# dda.net
KiCad netlist of a schematic drawn in EAGLE
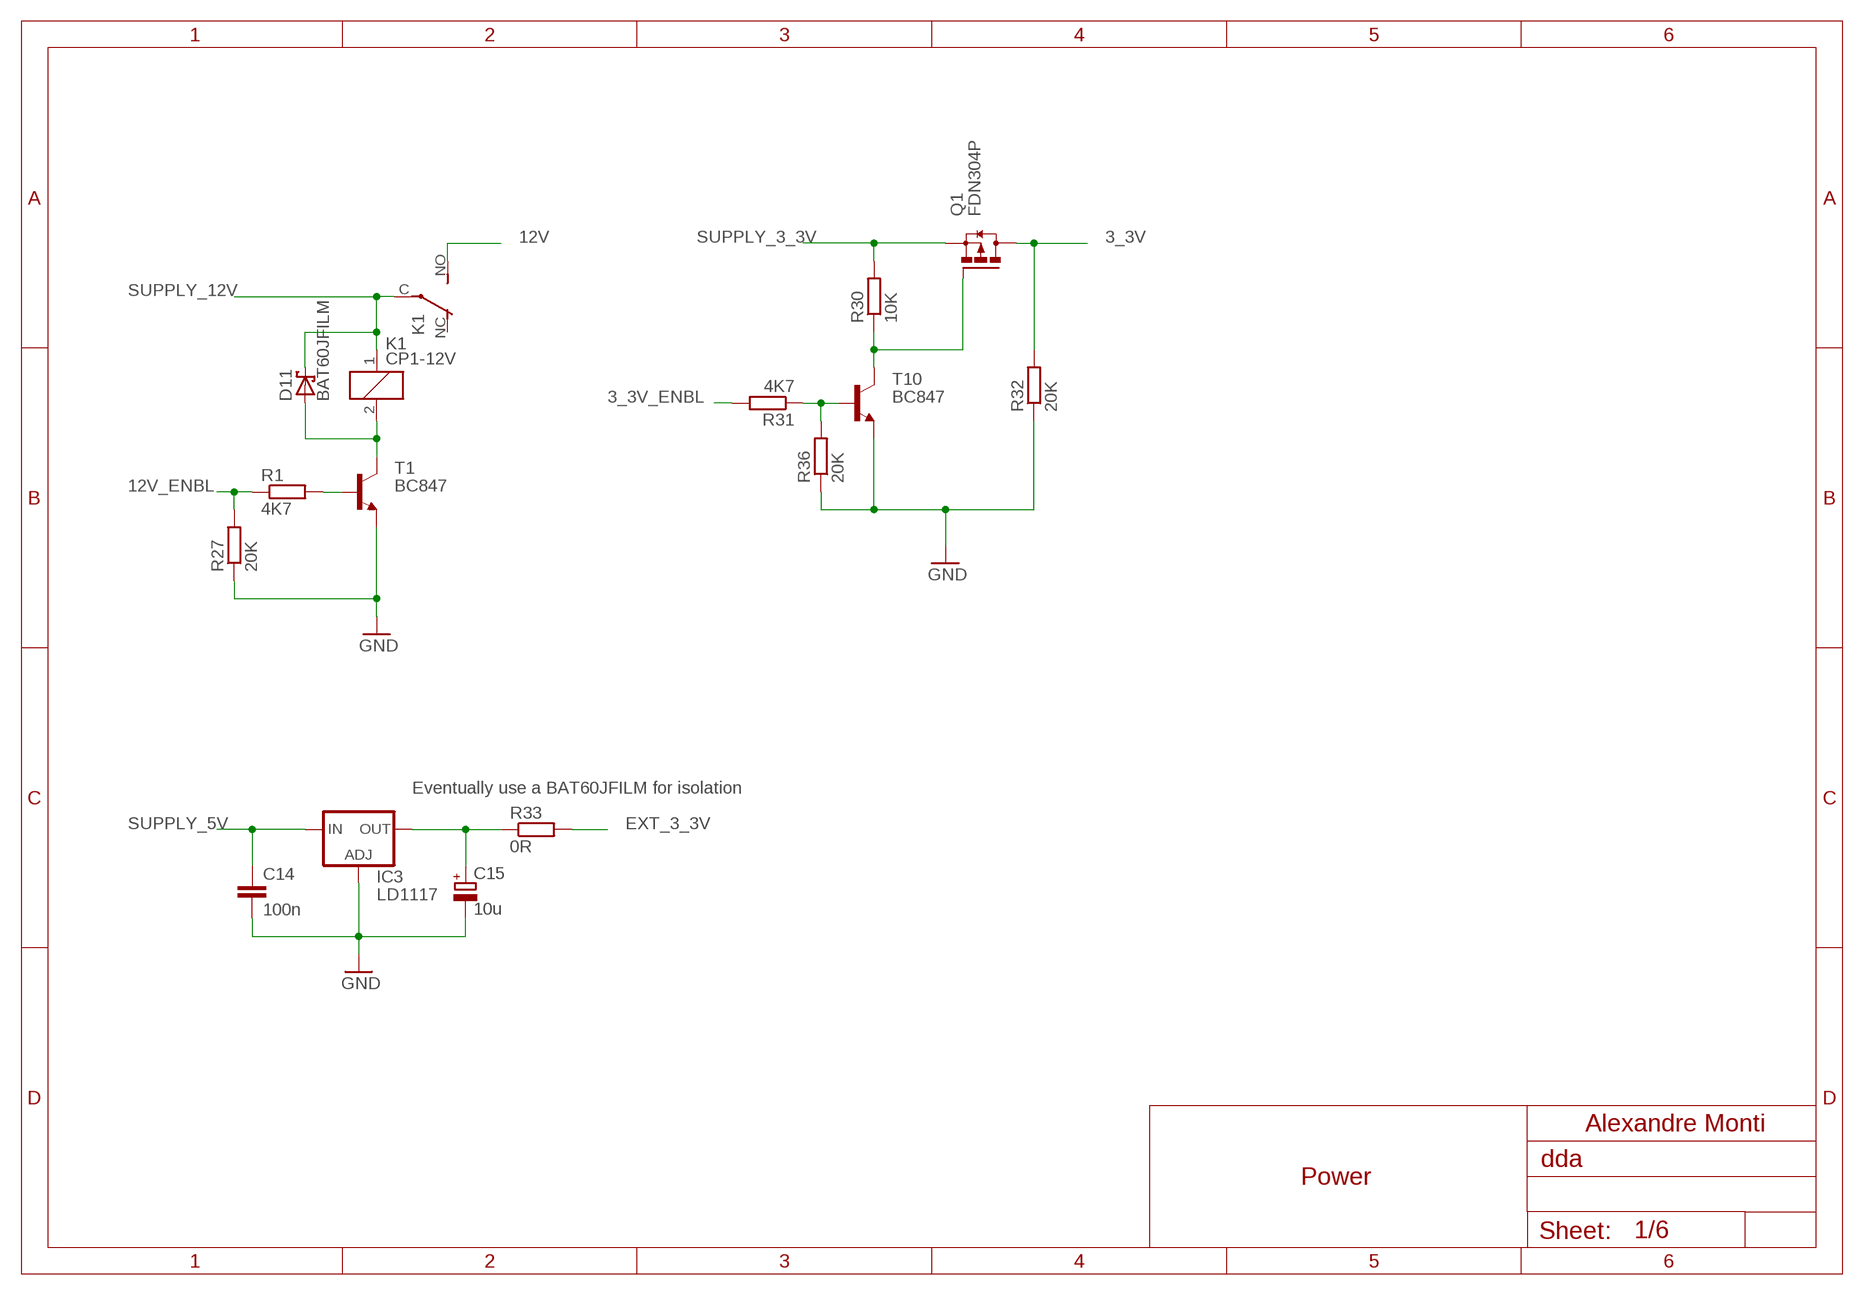
[diagram p0: schematic, sheet 1]
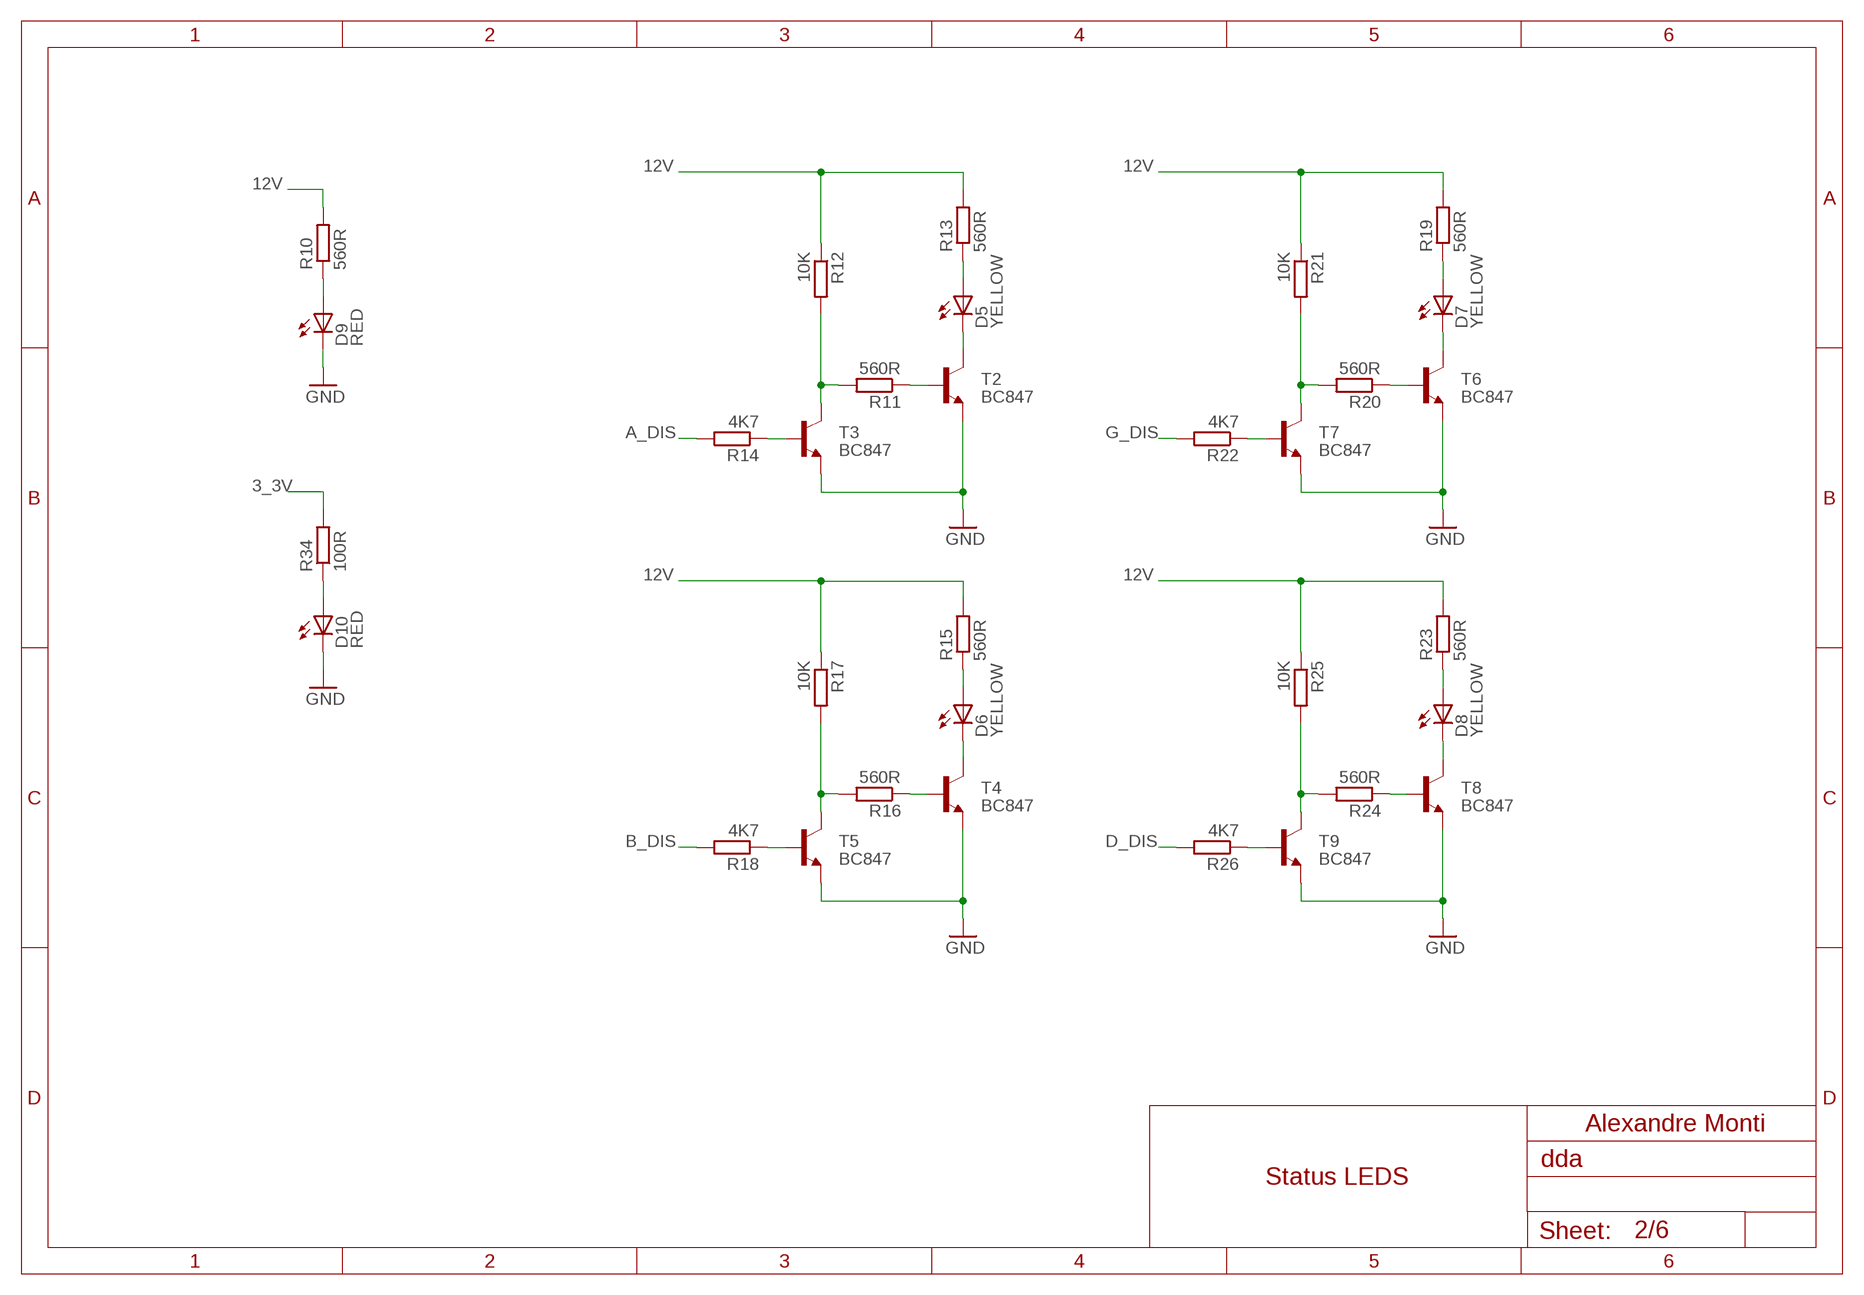
[diagram p1: schematic, sheet 2]
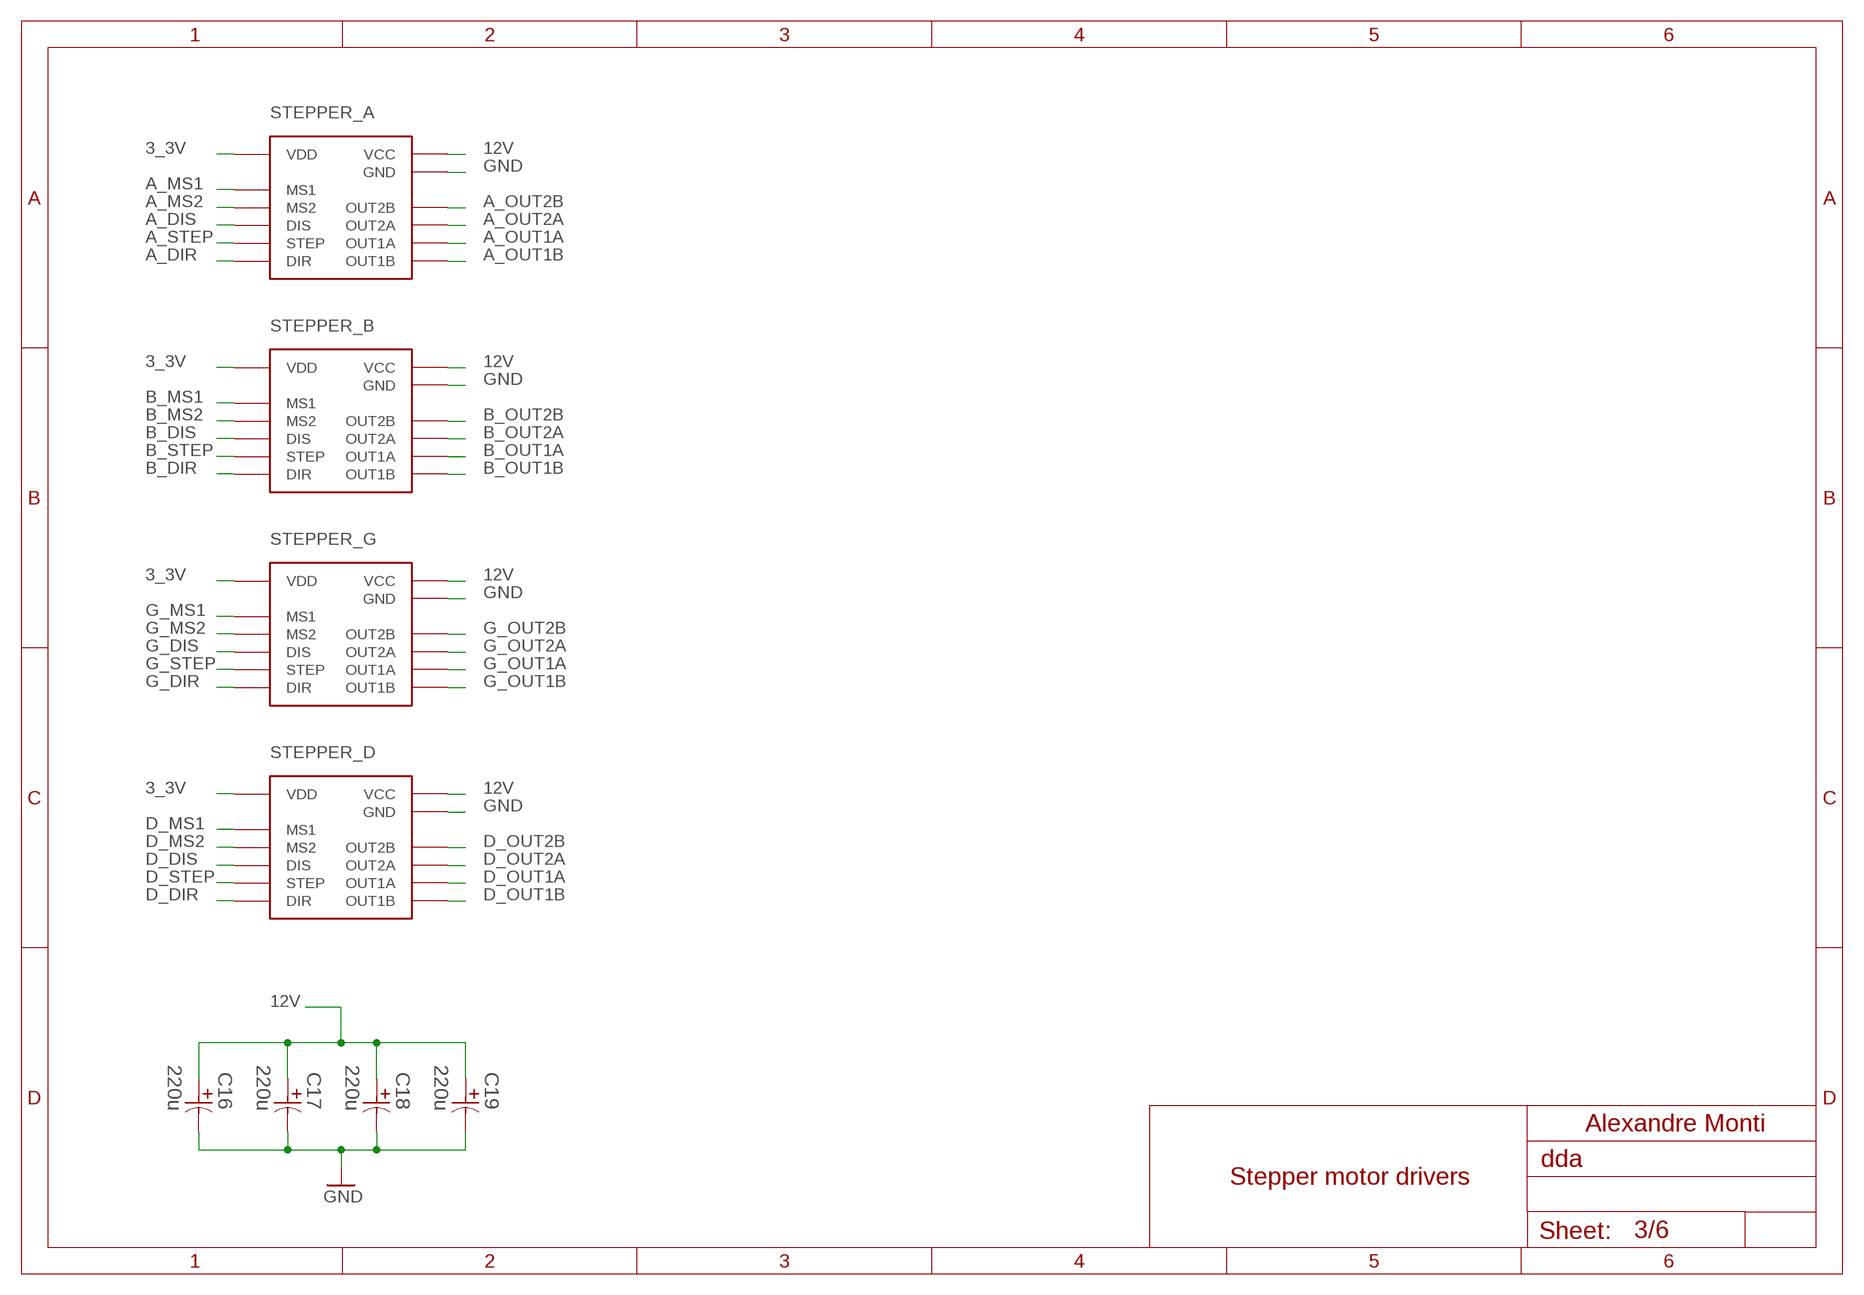
[diagram p2: schematic, sheet 3]
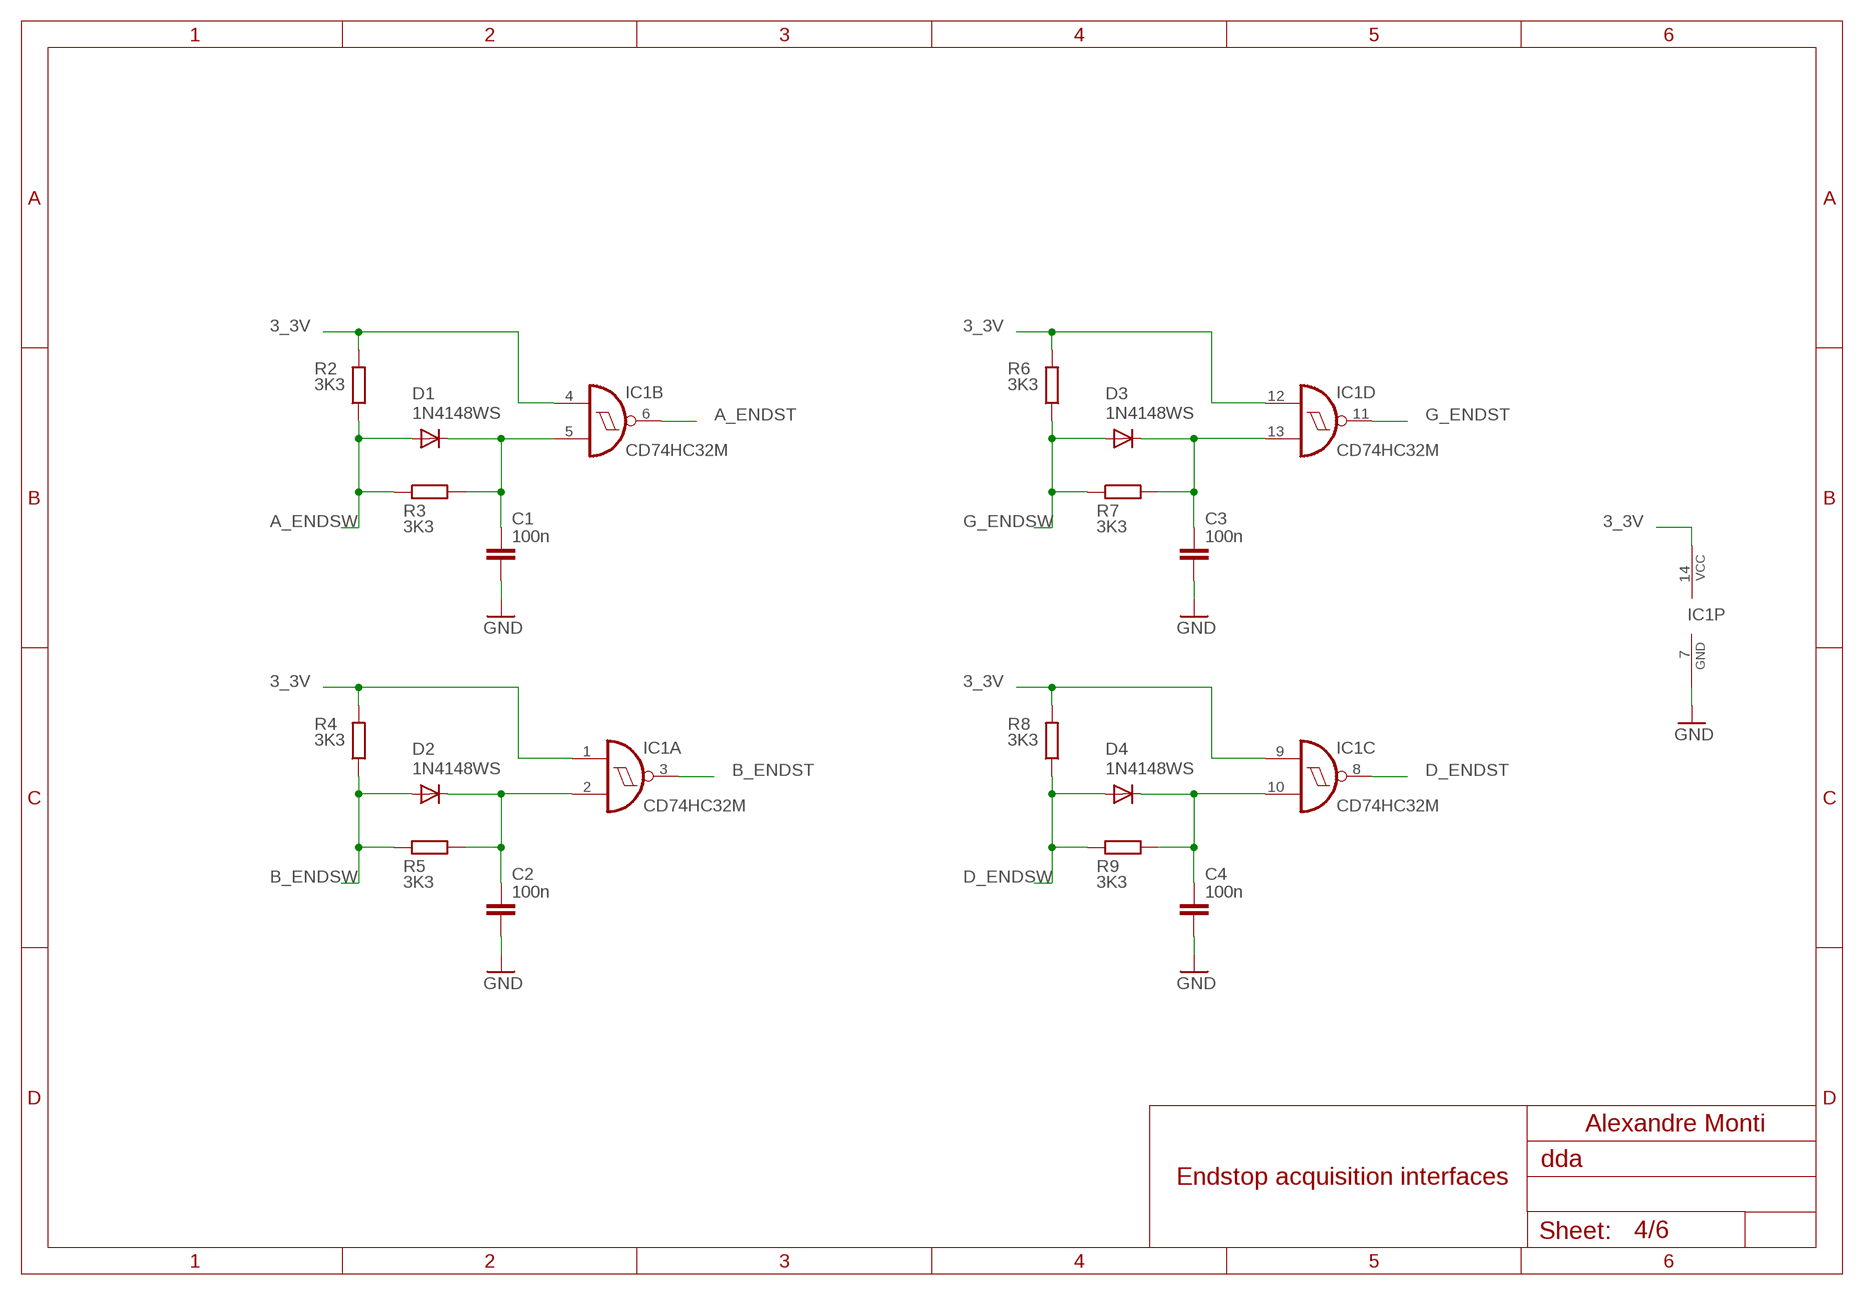
[diagram p3: schematic, sheet 4]
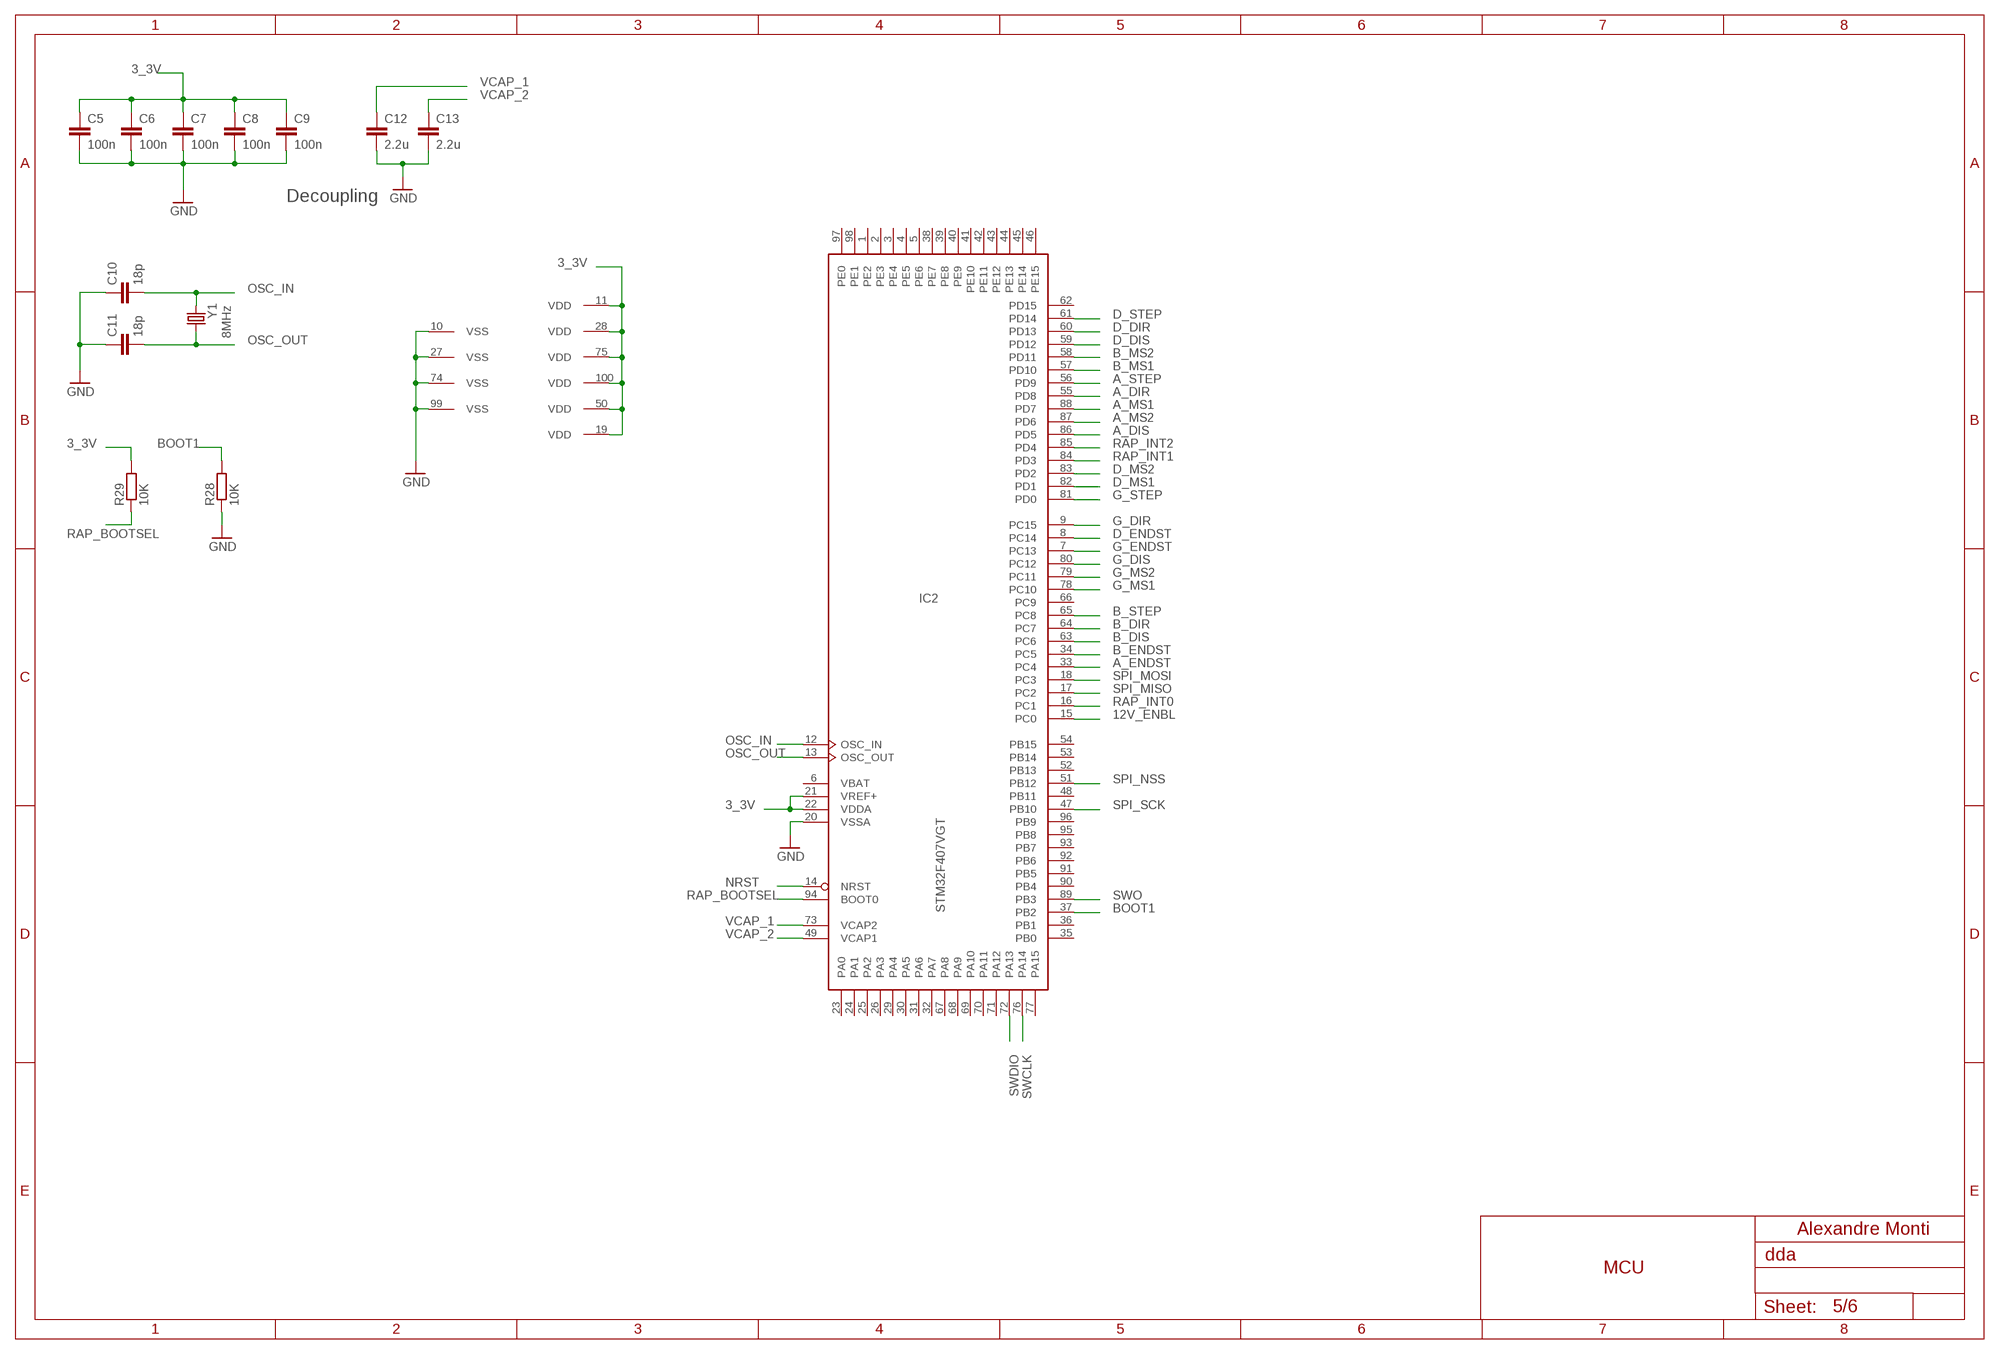
[diagram p4: schematic, sheet 5]
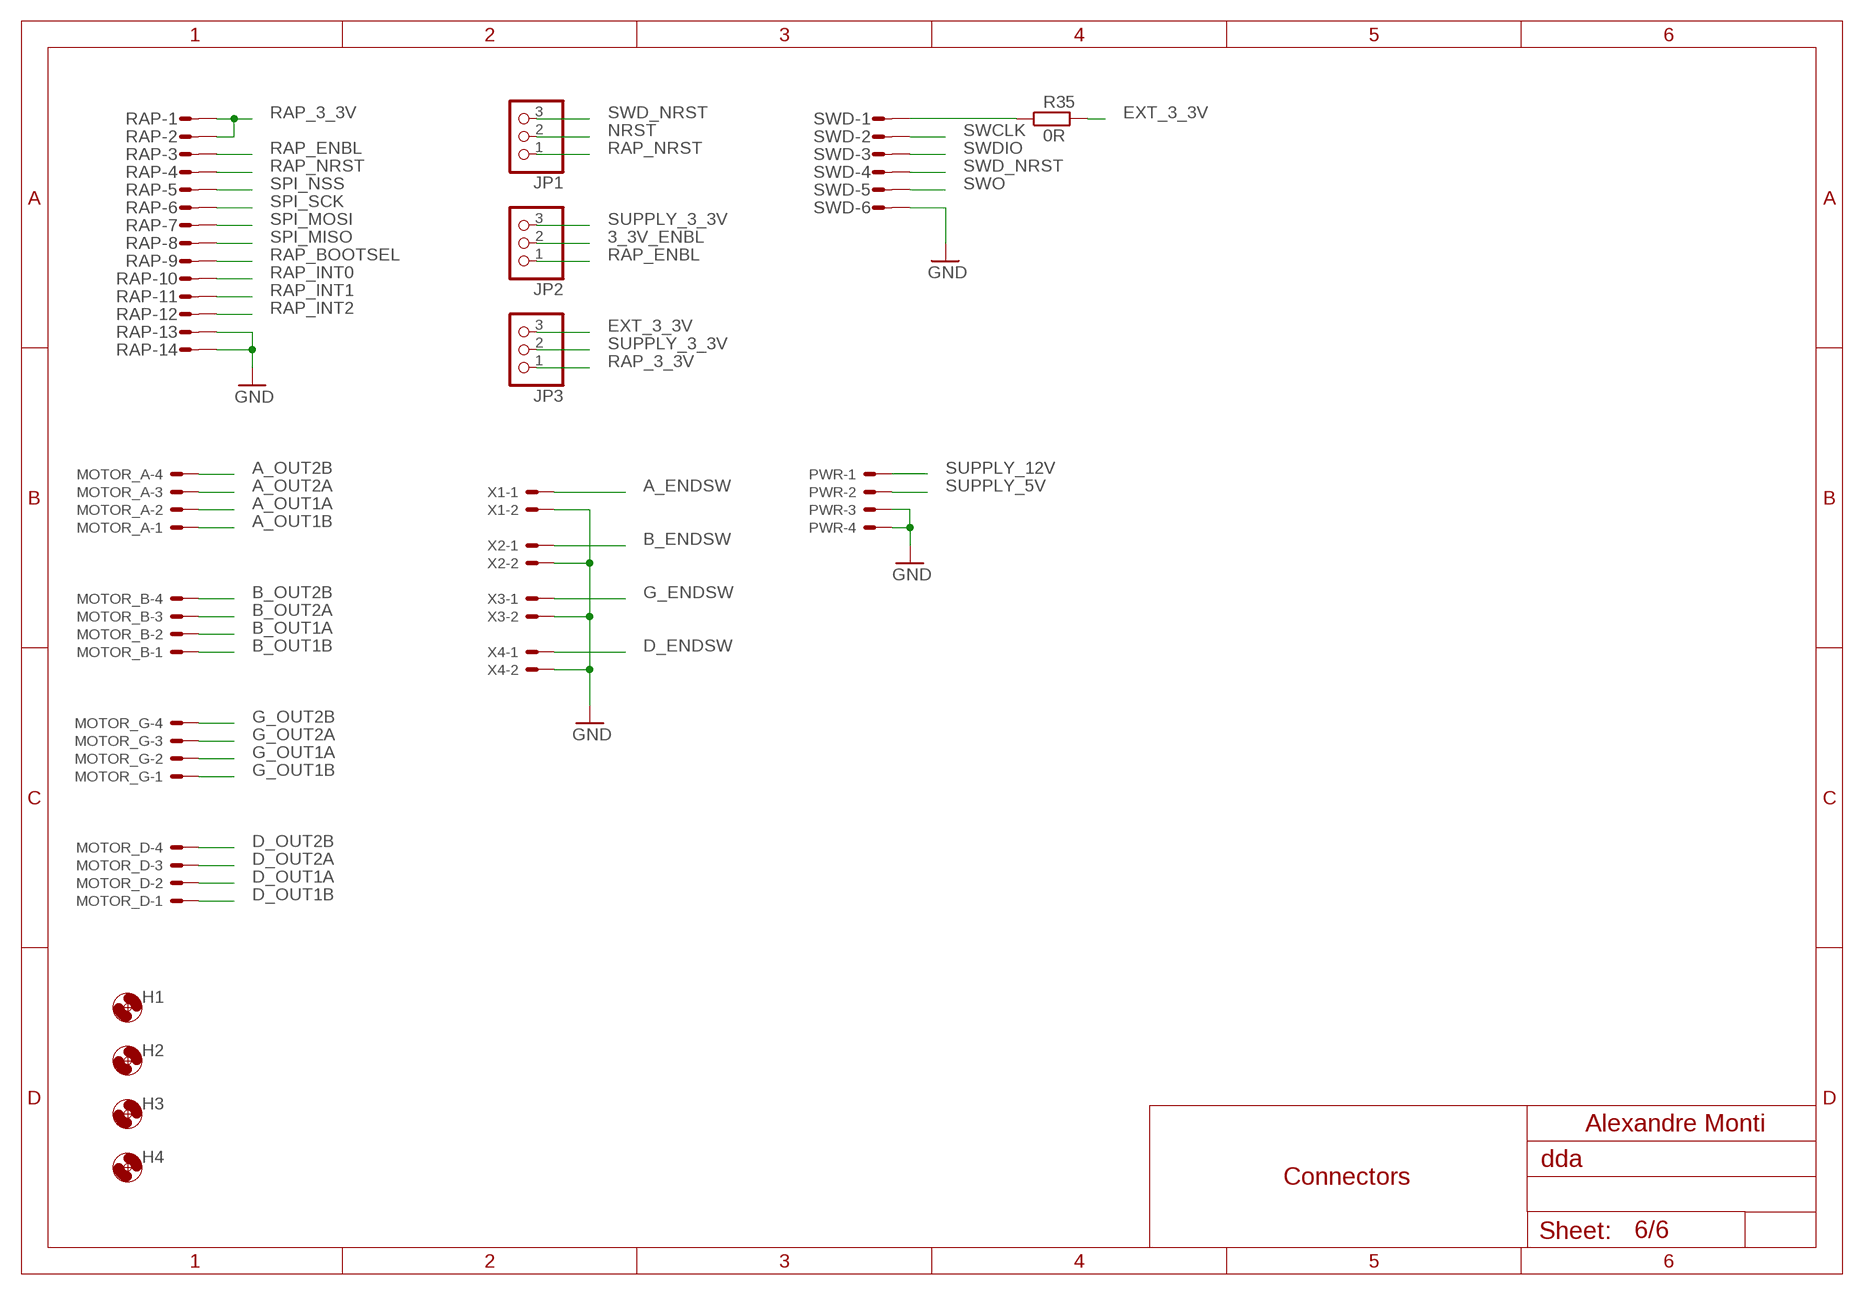
[diagram p5: schematic, sheet 6]

(export (version "E")
  (design (tool "Eeschema 10.0.6"))
  (components
    (comp (ref "H1")
      (value "MOUNT-HOLE3.2")
      (footprint "eagle-import:3,2")
      (libsource (lib "eagle-import") (part "MOUNT-HOLE3.2"))
    )
    (comp (ref "H2")
      (value "MOUNT-HOLE3.2")
      (footprint "eagle-import:3,2")
      (libsource (lib "eagle-import") (part "MOUNT-HOLE3.2"))
    )
    (comp (ref "H3")
      (value "MOUNT-HOLE3.2")
      (footprint "eagle-import:3,2")
      (libsource (lib "eagle-import") (part "MOUNT-HOLE3.2"))
    )
    (comp (ref "H4")
      (value "MOUNT-HOLE3.2")
      (footprint "eagle-import:3,2")
      (libsource (lib "eagle-import") (part "MOUNT-HOLE3.2"))
    )
    (comp (ref "JP1")
      (value "PINHD-1X03_2.00")
      (footprint "eagle-import:1X03M")
      (fields (field (name "PARTNO") "2289777"))
      (libsource (lib "eagle-import") (part "PINHD-1X03_2.00"))
    )
    (comp (ref "JP2")
      (value "PINHD-1X03_2.00")
      (footprint "eagle-import:1X03M")
      (fields (field (name "PARTNO") "2289777"))
      (libsource (lib "eagle-import") (part "PINHD-1X03_2.00"))
    )
    (comp (ref "JP3")
      (value "PINHD-1X03_2.00")
      (footprint "eagle-import:1X03M")
      (fields (field (name "PARTNO") "2289777"))
      (libsource (lib "eagle-import") (part "PINHD-1X03_2.00"))
    )
    (comp (ref "MOTOR_A")
      (value "22-23-2041")
      (footprint "eagle-import:22-23-2041")
      (fields (field (name "MF") "MOLEX") (field (name "PARTNO") "588593"))
      (libsource (lib "eagle-import") (part "22-23-2041"))
    )
    (comp (ref "MOTOR_B")
      (value "22-23-2041")
      (footprint "eagle-import:22-23-2041")
      (fields (field (name "MF") "MOLEX") (field (name "PARTNO") "588593"))
      (libsource (lib "eagle-import") (part "22-23-2041"))
    )
    (comp (ref "MOTOR_D")
      (value "22-23-2041")
      (footprint "eagle-import:22-23-2041")
      (fields (field (name "MF") "MOLEX") (field (name "PARTNO") "588593"))
      (libsource (lib "eagle-import") (part "22-23-2041"))
    )
    (comp (ref "MOTOR_G")
      (value "22-23-2041")
      (footprint "eagle-import:22-23-2041")
      (fields (field (name "MF") "MOLEX") (field (name "PARTNO") "588593"))
      (libsource (lib "eagle-import") (part "22-23-2041"))
    )
    (comp (ref "PWR")
      (value "22-23-2041")
      (footprint "eagle-import:22-23-2041")
      (fields (field (name "MF") "MOLEX") (field (name "PARTNO") "588593"))
      (libsource (lib "eagle-import") (part "22-23-2041"))
    )
    (comp (ref "R35")
      (value "0R")
      (footprint "eagle-import:R0805W")
      (fields (field (name "PARTNO") "9333681"))
      (libsource (lib "eagle-import") (part "R-EU_R0805W"))
    )
    (comp (ref "RAP")
      (value "MICROMATCH-14")
      (footprint "eagle-import:MICROMATCH-14")
      (fields
        (field (name "MF") "FARNELL")
        (field (name "MPN") "8-215464-4")
        (field (name "MATE_PARTNO") "149135")
        (field (name "PARTNO") "2308807")
      )
      (libsource (lib "eagle-import") (part "MICROMATCH-14"))
    )
    (comp (ref "SWD")
      (value "MICROMATCH-6")
      (footprint "eagle-import:MICROMATCH-6")
      (fields
        (field (name "MPN") "7-215464-6")
        (field (name "MATE_PARTNO") "149068")
        (field (name "PARTNO") "2473349")
      )
      (libsource (lib "eagle-import") (part "MICROMATCH-6"))
    )
    (comp (ref "X1")
      (value "22-23-2021")
      (footprint "eagle-import:22-23-2021")
      (fields (field (name "MF") "MOLEX") (field (name "PARTNO") "588570"))
      (libsource (lib "eagle-import") (part "22-23-2021"))
    )
    (comp (ref "X2")
      (value "22-23-2021")
      (footprint "eagle-import:22-23-2021")
      (fields (field (name "MF") "MOLEX") (field (name "PARTNO") "588570"))
      (libsource (lib "eagle-import") (part "22-23-2021"))
    )
    (comp (ref "X3")
      (value "22-23-2021")
      (footprint "eagle-import:22-23-2021")
      (fields (field (name "MF") "MOLEX") (field (name "PARTNO") "588570"))
      (libsource (lib "eagle-import") (part "22-23-2021"))
    )
    (comp (ref "X4")
      (value "22-23-2021")
      (footprint "eagle-import:22-23-2021")
      (fields (field (name "MF") "MOLEX") (field (name "PARTNO") "588570"))
      (libsource (lib "eagle-import") (part "22-23-2021"))
    )
    (comp (ref "C14")
      (value "100n")
      (footprint "eagle-import:C0805")
      (fields (field (name "PARTNO") "2496944"))
      (libsource (lib "eagle-import") (part "C-EUC0805"))
    )
    (comp (ref "C15")
      (value "10u")
      (footprint "eagle-import:CT3216")
      (fields (field (name "PARTNO") "1432339"))
      (libsource (lib "eagle-import") (part "CPOL-EUCT3216"))
    )
    (comp (ref "D11")
      (value "BAT60JFILM")
      (footprint "eagle-import:SOD323_ST")
      (fields (field (name "PARTNO") "1467544"))
      (libsource (lib "eagle-import") (part "BAT60J"))
    )
    (comp (ref "IC3")
      (value "LD1117")
      (footprint "eagle-import:SOT223")
      (fields (field (name "PARTNO") "1202826"))
      (libsource (lib "eagle-import") (part "LD117A?S12TR"))
    )
    (comp (ref "K1")
      (value "CP1-12V")
      (footprint "eagle-import:CP1")
      (fields (field (name "MF") "AROMAT/ MATSUSHITA") (field (name "PARTNO") "2103582"))
      (libsource (lib "eagle-import") (part "CP1?-12V"))
    )
    (comp (ref "Q1")
      (value "FDN304P")
      (footprint "eagle-import:SUPER-SOT3")
      (fields (field (name "PARTNO") "9846298"))
      (libsource (lib "eagle-import") (part "FDN360P"))
    )
    (comp (ref "R1")
      (value "4K7")
      (footprint "eagle-import:M0805")
      (fields (field (name "PARTNO") "9333266"))
      (libsource (lib "eagle-import") (part "R-EU_M0805"))
    )
    (comp (ref "R27")
      (value "20K")
      (footprint "eagle-import:M0805")
      (fields (field (name "PARTNO") "9332774"))
      (libsource (lib "eagle-import") (part "R-EU_M0805"))
    )
    (comp (ref "R30")
      (value "10K")
      (footprint "eagle-import:M0805")
      (fields (field (name "PARTNO") "9332391"))
      (libsource (lib "eagle-import") (part "R-EU_M0805"))
    )
    (comp (ref "R31")
      (value "4K7")
      (footprint "eagle-import:M0805")
      (fields (field (name "PARTNO") "9333266"))
      (libsource (lib "eagle-import") (part "R-EU_M0805"))
    )
    (comp (ref "R32")
      (value "20K")
      (footprint "eagle-import:M0805")
      (fields (field (name "PARTNO") "9332774"))
      (libsource (lib "eagle-import") (part "R-EU_M0805"))
    )
    (comp (ref "R33")
      (value "0R")
      (footprint "eagle-import:R0805W")
      (fields (field (name "PARTNO") "9333681"))
      (libsource (lib "eagle-import") (part "R-EU_R0805W"))
    )
    (comp (ref "R36")
      (value "20K")
      (footprint "eagle-import:M0805")
      (fields (field (name "PARTNO") "9332774"))
      (libsource (lib "eagle-import") (part "R-EU_M0805"))
    )
    (comp (ref "T1")
      (value "BC847")
      (footprint "eagle-import:SOT23")
      (fields (field (name "PARTNO") "2432696"))
      (libsource (lib "eagle-import") (part "BC847"))
    )
    (comp (ref "T10")
      (value "BC847")
      (footprint "eagle-import:SOT23")
      (fields (field (name "PARTNO") "2432696"))
      (libsource (lib "eagle-import") (part "BC847"))
    )
    (comp (ref "C5")
      (value "100n")
      (footprint "eagle-import:C0805")
      (fields (field (name "PARTNO") "2496944"))
      (libsource (lib "eagle-import") (part "C-EUC0805"))
    )
    (comp (ref "C6")
      (value "100n")
      (footprint "eagle-import:C0805")
      (fields (field (name "PARTNO") "2496944"))
      (libsource (lib "eagle-import") (part "C-EUC0805"))
    )
    (comp (ref "C7")
      (value "100n")
      (footprint "eagle-import:C0805")
      (fields (field (name "PARTNO") "2496944"))
      (libsource (lib "eagle-import") (part "C-EUC0805"))
    )
    (comp (ref "C8")
      (value "100n")
      (footprint "eagle-import:C0805")
      (fields (field (name "PARTNO") "2496944"))
      (libsource (lib "eagle-import") (part "C-EUC0805"))
    )
    (comp (ref "C9")
      (value "100n")
      (footprint "eagle-import:C0805")
      (fields (field (name "PARTNO") "2496944"))
      (libsource (lib "eagle-import") (part "C-EUC0805"))
    )
    (comp (ref "C10")
      (value "18p")
      (footprint "eagle-import:C0805")
      (fields (field (name "PARTNO") "1414673"))
      (libsource (lib "eagle-import") (part "C-EUC0805"))
    )
    (comp (ref "C11")
      (value "18p")
      (footprint "eagle-import:C0805")
      (fields (field (name "PARTNO") "1414673"))
      (libsource (lib "eagle-import") (part "C-EUC0805"))
    )
    (comp (ref "C12")
      (value "2.2u")
      (footprint "eagle-import:C1206")
      (fields (field (name "PARTNO") "1759477"))
      (libsource (lib "eagle-import") (part "C-EUC1206"))
    )
    (comp (ref "C13")
      (value "2.2u")
      (footprint "eagle-import:C1206")
      (fields (field (name "PARTNO") "1759477"))
      (libsource (lib "eagle-import") (part "C-EUC1206"))
    )
    (comp (ref "IC2")
      (value "STM32F407VGT")
      (footprint "eagle-import:LQFP100")
      (fields (field (name "PARTNO") "2064368"))
      (libsource (lib "eagle-import") (part "STM32F407VTG"))
    )
    (comp (ref "R28")
      (value "10K")
      (footprint "eagle-import:M0805")
      (fields (field (name "PARTNO") "9332391"))
      (libsource (lib "eagle-import") (part "R-EU_M0805"))
    )
    (comp (ref "R29")
      (value "10K")
      (footprint "eagle-import:M0805")
      (fields (field (name "PARTNO") "9332391"))
      (libsource (lib "eagle-import") (part "R-EU_M0805"))
    )
    (comp (ref "Y1")
      (value "8MHz")
      (footprint "eagle-import:CRYSTAL-SMD-5X3.2")
      (fields (field (name "PARTNO") "2101329"))
      (libsource (lib "eagle-import") (part "CRYSTAL5X3.2"))
    )
    (comp (ref "D5")
      (value "YELLOW")
      (footprint "eagle-import:CHIP-LED0805")
      (fields (field (name "PARTNO") "1581241"))
      (libsource (lib "eagle-import") (part "LEDCHIP-LED0805"))
    )
    (comp (ref "D6")
      (value "YELLOW")
      (footprint "eagle-import:CHIP-LED0805")
      (fields (field (name "PARTNO") "1581241"))
      (libsource (lib "eagle-import") (part "LEDCHIP-LED0805"))
    )
    (comp (ref "D7")
      (value "YELLOW")
      (footprint "eagle-import:CHIP-LED0805")
      (fields (field (name "PARTNO") "1581241"))
      (libsource (lib "eagle-import") (part "LEDCHIP-LED0805"))
    )
    (comp (ref "D8")
      (value "YELLOW")
      (footprint "eagle-import:CHIP-LED0805")
      (fields (field (name "PARTNO") "1581241"))
      (libsource (lib "eagle-import") (part "LEDCHIP-LED0805"))
    )
    (comp (ref "D9")
      (value "RED")
      (footprint "eagle-import:CHIP-LED0805")
      (fields (field (name "PARTNO") "1581239"))
      (libsource (lib "eagle-import") (part "LEDCHIP-LED0805"))
    )
    (comp (ref "D10")
      (value "RED")
      (footprint "eagle-import:CHIP-LED0805")
      (fields (field (name "PARTNO") "1581239"))
      (libsource (lib "eagle-import") (part "LEDCHIP-LED0805"))
    )
    (comp (ref "R10")
      (value "560R")
      (footprint "eagle-import:M0805")
      (fields (field (name "PARTNO") "9334688"))
      (libsource (lib "eagle-import") (part "R-EU_M0805"))
    )
    (comp (ref "R11")
      (value "560R")
      (footprint "eagle-import:M0805")
      (fields (field (name "PARTNO") "9334688"))
      (libsource (lib "eagle-import") (part "R-EU_M0805"))
    )
    (comp (ref "R12")
      (value "10K")
      (footprint "eagle-import:M0805")
      (fields (field (name "PARTNO") "9332391"))
      (libsource (lib "eagle-import") (part "R-EU_M0805"))
    )
    (comp (ref "R13")
      (value "560R")
      (footprint "eagle-import:M0805")
      (fields (field (name "PARTNO") "9334688"))
      (libsource (lib "eagle-import") (part "R-EU_M0805"))
    )
    (comp (ref "R14")
      (value "4K7")
      (footprint "eagle-import:M0805")
      (fields (field (name "PARTNO") "9333266"))
      (libsource (lib "eagle-import") (part "R-EU_M0805"))
    )
    (comp (ref "R15")
      (value "560R")
      (footprint "eagle-import:M0805")
      (fields (field (name "PARTNO") "9334688"))
      (libsource (lib "eagle-import") (part "R-EU_M0805"))
    )
    (comp (ref "R16")
      (value "560R")
      (footprint "eagle-import:M0805")
      (fields (field (name "PARTNO") "9334688"))
      (libsource (lib "eagle-import") (part "R-EU_M0805"))
    )
    (comp (ref "R17")
      (value "10K")
      (footprint "eagle-import:M0805")
      (fields (field (name "PARTNO") "9332391"))
      (libsource (lib "eagle-import") (part "R-EU_M0805"))
    )
    (comp (ref "R18")
      (value "4K7")
      (footprint "eagle-import:M0805")
      (fields (field (name "PARTNO") "9333266"))
      (libsource (lib "eagle-import") (part "R-EU_M0805"))
    )
    (comp (ref "R19")
      (value "560R")
      (footprint "eagle-import:M0805")
      (fields (field (name "PARTNO") "9334688"))
      (libsource (lib "eagle-import") (part "R-EU_M0805"))
    )
    (comp (ref "R20")
      (value "560R")
      (footprint "eagle-import:M0805")
      (fields (field (name "PARTNO") "9334688"))
      (libsource (lib "eagle-import") (part "R-EU_M0805"))
    )
    (comp (ref "R21")
      (value "10K")
      (footprint "eagle-import:M0805")
      (fields (field (name "PARTNO") "9332391"))
      (libsource (lib "eagle-import") (part "R-EU_M0805"))
    )
    (comp (ref "R22")
      (value "4K7")
      (footprint "eagle-import:M0805")
      (fields (field (name "PARTNO") "9333266"))
      (libsource (lib "eagle-import") (part "R-EU_M0805"))
    )
    (comp (ref "R23")
      (value "560R")
      (footprint "eagle-import:M0805")
      (fields (field (name "PARTNO") "9334688"))
      (libsource (lib "eagle-import") (part "R-EU_M0805"))
    )
    (comp (ref "R24")
      (value "560R")
      (footprint "eagle-import:M0805")
      (fields (field (name "PARTNO") "9334688"))
      (libsource (lib "eagle-import") (part "R-EU_M0805"))
    )
    (comp (ref "R25")
      (value "10K")
      (footprint "eagle-import:M0805")
      (fields (field (name "PARTNO") "9332391"))
      (libsource (lib "eagle-import") (part "R-EU_M0805"))
    )
    (comp (ref "R26")
      (value "4K7")
      (footprint "eagle-import:M0805")
      (fields (field (name "PARTNO") "9333266"))
      (libsource (lib "eagle-import") (part "R-EU_M0805"))
    )
    (comp (ref "R34")
      (value "100R")
      (footprint "eagle-import:M0805")
      (fields (field (name "PARTNO") "9237364"))
      (libsource (lib "eagle-import") (part "R-EU_M0805"))
    )
    (comp (ref "T2")
      (value "BC847")
      (footprint "eagle-import:SOT23")
      (fields (field (name "PARTNO") "2432696"))
      (libsource (lib "eagle-import") (part "BC847"))
    )
    (comp (ref "T3")
      (value "BC847")
      (footprint "eagle-import:SOT23")
      (fields (field (name "PARTNO") "2432696"))
      (libsource (lib "eagle-import") (part "BC847"))
    )
    (comp (ref "T4")
      (value "BC847")
      (footprint "eagle-import:SOT23")
      (fields (field (name "PARTNO") "2432696"))
      (libsource (lib "eagle-import") (part "BC847"))
    )
    (comp (ref "T5")
      (value "BC847")
      (footprint "eagle-import:SOT23")
      (fields (field (name "PARTNO") "2432696"))
      (libsource (lib "eagle-import") (part "BC847"))
    )
    (comp (ref "T6")
      (value "BC847")
      (footprint "eagle-import:SOT23")
      (fields (field (name "PARTNO") "2432696"))
      (libsource (lib "eagle-import") (part "BC847"))
    )
    (comp (ref "T7")
      (value "BC847")
      (footprint "eagle-import:SOT23")
      (fields (field (name "PARTNO") "2432696"))
      (libsource (lib "eagle-import") (part "BC847"))
    )
    (comp (ref "T8")
      (value "BC847")
      (footprint "eagle-import:SOT23")
      (fields (field (name "PARTNO") "2432696"))
      (libsource (lib "eagle-import") (part "BC847"))
    )
    (comp (ref "T9")
      (value "BC847")
      (footprint "eagle-import:SOT23")
      (fields (field (name "PARTNO") "2432696"))
      (libsource (lib "eagle-import") (part "BC847"))
    )
    (comp (ref "C16")
      (value "220u")
      (footprint "eagle-import:CAPAE660X800N")
      (fields
        (field (name "MPN") "EEE-FTE221XAP")
        (field (name "TOLERANCE") "±20 %")
        (field (name "PARTNO") "1868409")
      )
      (libsource (lib "eagle-import") (part "EEE--CASE-D8FTE221XAP"))
    )
    (comp (ref "C17")
      (value "220u")
      (footprint "eagle-import:CAPAE660X800N")
      (fields
        (field (name "MPN") "EEE-FTE221XAP")
        (field (name "TOLERANCE") "±20 %")
        (field (name "PARTNO") "1868409")
      )
      (libsource (lib "eagle-import") (part "EEE--CASE-D8FTE221XAP"))
    )
    (comp (ref "C18")
      (value "220u")
      (footprint "eagle-import:CAPAE660X800N")
      (fields
        (field (name "MPN") "EEE-FTE221XAP")
        (field (name "TOLERANCE") "±20 %")
        (field (name "PARTNO") "1868409")
      )
      (libsource (lib "eagle-import") (part "EEE--CASE-D8FTE221XAP"))
    )
    (comp (ref "C19")
      (value "220u")
      (footprint "eagle-import:CAPAE660X800N")
      (fields
        (field (name "MPN") "EEE-FTE221XAP")
        (field (name "TOLERANCE") "±20 %")
        (field (name "PARTNO") "1868409")
      )
      (libsource (lib "eagle-import") (part "EEE--CASE-D8FTE221XAP"))
    )
    (comp (ref "STEPPER_A")
      (value "REPICO_STEPPER")
      (footprint "eagle-import:REPICO_STEPPER")
      (fields (field (name "PARTNO") "1593462"))
      (libsource (lib "eagle-import") (part "REPICO_STEPPER"))
    )
    (comp (ref "STEPPER_B")
      (value "REPICO_STEPPER")
      (footprint "eagle-import:REPICO_STEPPER")
      (fields (field (name "PARTNO") "1593462"))
      (libsource (lib "eagle-import") (part "REPICO_STEPPER"))
    )
    (comp (ref "STEPPER_D")
      (value "REPICO_STEPPER")
      (footprint "eagle-import:REPICO_STEPPER")
      (fields (field (name "PARTNO") "1593462"))
      (libsource (lib "eagle-import") (part "REPICO_STEPPER"))
    )
    (comp (ref "STEPPER_G")
      (value "REPICO_STEPPER")
      (footprint "eagle-import:REPICO_STEPPER")
      (fields (field (name "PARTNO") "1593462"))
      (libsource (lib "eagle-import") (part "REPICO_STEPPER"))
    )
    (comp (ref "C1")
      (value "100n")
      (footprint "eagle-import:C0805")
      (fields (field (name "PARTNO") "2496944"))
      (libsource (lib "eagle-import") (part "C-EUC0805"))
    )
    (comp (ref "C2")
      (value "100n")
      (footprint "eagle-import:C0805")
      (fields (field (name "PARTNO") "2496944"))
      (libsource (lib "eagle-import") (part "C-EUC0805"))
    )
    (comp (ref "C3")
      (value "100n")
      (footprint "eagle-import:C0805")
      (fields (field (name "PARTNO") "2496944"))
      (libsource (lib "eagle-import") (part "C-EUC0805"))
    )
    (comp (ref "C4")
      (value "100n")
      (footprint "eagle-import:C0805")
      (fields (field (name "PARTNO") "2496944"))
      (libsource (lib "eagle-import") (part "C-EUC0805"))
    )
    (comp (ref "D1")
      (value "1N4148WS")
      (footprint "eagle-import:SOD123")
      (fields (field (name "PARTNO") "1466524"))
      (libsource (lib "eagle-import") (part "DIODE-SOD123"))
    )
    (comp (ref "D2")
      (value "1N4148WS")
      (footprint "eagle-import:SOD123")
      (fields (field (name "PARTNO") "1466524"))
      (libsource (lib "eagle-import") (part "DIODE-SOD123"))
    )
    (comp (ref "D3")
      (value "1N4148WS")
      (footprint "eagle-import:SOD123")
      (fields (field (name "PARTNO") "1466524"))
      (libsource (lib "eagle-import") (part "DIODE-SOD123"))
    )
    (comp (ref "D4")
      (value "1N4148WS")
      (footprint "eagle-import:SOD123")
      (fields (field (name "PARTNO") "1466524"))
      (libsource (lib "eagle-import") (part "DIODE-SOD123"))
    )
    (comp (ref "IC1")
      (value "CD74HC32M")
      (footprint "eagle-import:SO14")
      (fields (field (name "PARTNO") "1103158"))
      (libsource (lib "eagle-import") (part "74132DLS"))
    )
    (comp (ref "R2")
      (value "3K3")
      (footprint "eagle-import:M0805")
      (fields (field (name "PARTNO") "9333045"))
      (libsource (lib "eagle-import") (part "R-EU_M0805"))
    )
    (comp (ref "R3")
      (value "3K3")
      (footprint "eagle-import:M0805")
      (fields (field (name "PARTNO") "9333045"))
      (libsource (lib "eagle-import") (part "R-EU_M0805"))
    )
    (comp (ref "R4")
      (value "3K3")
      (footprint "eagle-import:M0805")
      (fields (field (name "PARTNO") "9333045"))
      (libsource (lib "eagle-import") (part "R-EU_M0805"))
    )
    (comp (ref "R5")
      (value "3K3")
      (footprint "eagle-import:M0805")
      (fields (field (name "PARTNO") "9333045"))
      (libsource (lib "eagle-import") (part "R-EU_M0805"))
    )
    (comp (ref "R6")
      (value "3K3")
      (footprint "eagle-import:M0805")
      (fields (field (name "PARTNO") "9333045"))
      (libsource (lib "eagle-import") (part "R-EU_M0805"))
    )
    (comp (ref "R7")
      (value "3K3")
      (footprint "eagle-import:M0805")
      (fields (field (name "PARTNO") "9333045"))
      (libsource (lib "eagle-import") (part "R-EU_M0805"))
    )
    (comp (ref "R8")
      (value "3K3")
      (footprint "eagle-import:M0805")
      (fields (field (name "PARTNO") "9333045"))
      (libsource (lib "eagle-import") (part "R-EU_M0805"))
    )
    (comp (ref "R9")
      (value "3K3")
      (footprint "eagle-import:M0805")
      (fields (field (name "PARTNO") "9333045"))
      (libsource (lib "eagle-import") (part "R-EU_M0805"))
    )
  )
  (nets
    (net (code "1") (name "3_3V") (class "Default")
      (node (ref "C5") (pin "1") (pinfunction "1_1") (pintype "passive"))
      (node (ref "C6") (pin "1") (pinfunction "1_1") (pintype "passive"))
      (node (ref "C7") (pin "1") (pinfunction "1_1") (pintype "passive"))
      (node (ref "C8") (pin "1") (pinfunction "1_1") (pintype "passive"))
      (node (ref "C9") (pin "1") (pinfunction "1_1") (pintype "passive"))
      (node (ref "IC1") (pin "1") (pinfunction "I0_1") (pintype "input"))
      (node (ref "IC1") (pin "12") (pinfunction "I0_12") (pintype "input"))
      (node (ref "IC1") (pin "14") (pinfunction "VCC_14") (pintype "power_in"))
      (node (ref "IC1") (pin "4") (pinfunction "I0_4") (pintype "input"))
      (node (ref "IC1") (pin "9") (pinfunction "I0_9") (pintype "input"))
      (node (ref "IC2") (pin "100") (pinfunction "VDD_100") (pintype "power_in"))
      (node (ref "IC2") (pin "11") (pinfunction "VDD_11") (pintype "power_in"))
      (node (ref "IC2") (pin "19") (pinfunction "VDD_19") (pintype "power_in"))
      (node (ref "IC2") (pin "21") (pinfunction "VREF+_21") (pintype "power_in"))
      (node (ref "IC2") (pin "22") (pinfunction "VDDA_22") (pintype "power_in"))
      (node (ref "IC2") (pin "28") (pinfunction "VDD_28") (pintype "power_in"))
      (node (ref "IC2") (pin "50") (pinfunction "VDD_50") (pintype "power_in"))
      (node (ref "IC2") (pin "75") (pinfunction "VDD_75") (pintype "power_in"))
      (node (ref "Q1") (pin "3") (pinfunction "D_3") (pintype "passive"))
      (node (ref "R2") (pin "2") (pinfunction "2_2") (pintype "passive"))
      (node (ref "R29") (pin "2") (pinfunction "2_2") (pintype "passive"))
      (node (ref "R32") (pin "2") (pinfunction "2_2") (pintype "passive"))
      (node (ref "R34") (pin "2") (pinfunction "2_2") (pintype "passive"))
      (node (ref "R4") (pin "2") (pinfunction "2_2") (pintype "passive"))
      (node (ref "R6") (pin "2") (pinfunction "2_2") (pintype "passive"))
      (node (ref "R8") (pin "2") (pinfunction "2_2") (pintype "passive"))
      (node (ref "STEPPER_A") (pin "VDD") (pinfunction "VDD_VDD") (pintype "power_in"))
      (node (ref "STEPPER_B") (pin "VDD") (pinfunction "VDD_VDD") (pintype "power_in"))
      (node (ref "STEPPER_D") (pin "VDD") (pinfunction "VDD_VDD") (pintype "power_in"))
      (node (ref "STEPPER_G") (pin "VDD") (pinfunction "VDD_VDD") (pintype "power_in"))
    )
    (net (code "2") (name "3_3V_ENBL") (class "Default")
      (node (ref "JP2") (pin "2") (pinfunction "2_2") (pintype "passive"))
      (node (ref "R31") (pin "2") (pinfunction "2_2") (pintype "passive"))
    )
    (net (code "3") (name "12V") (class "Default")
      (node (ref "C16") (pin "1") (pinfunction "1_1") (pintype "passive"))
      (node (ref "C17") (pin "1") (pinfunction "1_1") (pintype "passive"))
      (node (ref "C18") (pin "1") (pinfunction "1_1") (pintype "passive"))
      (node (ref "C19") (pin "1") (pinfunction "1_1") (pintype "passive"))
      (node (ref "K1") (pin "NO") (pinfunction "S_NO") (pintype "passive"))
      (node (ref "R10") (pin "2") (pinfunction "2_2") (pintype "passive"))
      (node (ref "R12") (pin "1") (pinfunction "1_1") (pintype "passive"))
      (node (ref "R13") (pin "2") (pinfunction "2_2") (pintype "passive"))
      (node (ref "R15") (pin "2") (pinfunction "2_2") (pintype "passive"))
      (node (ref "R17") (pin "1") (pinfunction "1_1") (pintype "passive"))
      (node (ref "R19") (pin "2") (pinfunction "2_2") (pintype "passive"))
      (node (ref "R21") (pin "1") (pinfunction "1_1") (pintype "passive"))
      (node (ref "R23") (pin "2") (pinfunction "2_2") (pintype "passive"))
      (node (ref "R25") (pin "1") (pinfunction "1_1") (pintype "passive"))
      (node (ref "STEPPER_A") (pin "VCC") (pinfunction "VCC_VCC") (pintype "power_in"))
      (node (ref "STEPPER_B") (pin "VCC") (pinfunction "VCC_VCC") (pintype "power_in"))
      (node (ref "STEPPER_D") (pin "VCC") (pinfunction "VCC_VCC") (pintype "power_in"))
      (node (ref "STEPPER_G") (pin "VCC") (pinfunction "VCC_VCC") (pintype "power_in"))
    )
    (net (code "4") (name "12V_ENBL") (class "Default")
      (node (ref "IC2") (pin "15") (pinfunction "PC0_15") (pintype "bidirectional"))
      (node (ref "R1") (pin "1") (pinfunction "1_1") (pintype "passive"))
      (node (ref "R27") (pin "2") (pinfunction "2_2") (pintype "passive"))
    )
    (net (code "5") (name "A_DIR") (class "Default")
      (node (ref "IC2") (pin "55") (pinfunction "PD8_55") (pintype "bidirectional"))
      (node (ref "STEPPER_A") (pin "DIR") (pinfunction "DIR_DIR") (pintype "input"))
    )
    (net (code "6") (name "A_DIS") (class "Default")
      (node (ref "IC2") (pin "86") (pinfunction "PD5_86") (pintype "bidirectional"))
      (node (ref "R14") (pin "2") (pinfunction "2_2") (pintype "passive"))
      (node (ref "STEPPER_A") (pin "DIS") (pinfunction "DIS_DIS") (pintype "input"))
    )
    (net (code "7") (name "A_ENDST") (class "Default")
      (node (ref "IC1") (pin "6") (pinfunction "O_6") (pintype "output"))
      (node (ref "IC2") (pin "33") (pinfunction "PC4_33") (pintype "bidirectional"))
    )
    (net (code "8") (name "A_ENDSW") (class "Default")
      (node (ref "D1") (pin "A") (pinfunction "A_A") (pintype "passive"))
      (node (ref "R2") (pin "1") (pinfunction "1_1") (pintype "passive"))
      (node (ref "R3") (pin "1") (pinfunction "1_1") (pintype "passive"))
      (node (ref "X1") (pin "1") (pinfunction "S_1") (pintype "passive"))
    )
    (net (code "9") (name "A_MS1") (class "Default")
      (node (ref "IC2") (pin "88") (pinfunction "PD7_88") (pintype "bidirectional"))
      (node (ref "STEPPER_A") (pin "MS1") (pinfunction "MS1_MS1") (pintype "input"))
    )
    (net (code "10") (name "A_MS2") (class "Default")
      (node (ref "IC2") (pin "87") (pinfunction "PD6_87") (pintype "bidirectional"))
      (node (ref "STEPPER_A") (pin "MS2") (pinfunction "MS2_MS2") (pintype "input"))
    )
    (net (code "11") (name "A_OUT1A") (class "Default")
      (node (ref "MOTOR_A") (pin "2") (pinfunction "S_2") (pintype "passive"))
      (node (ref "STEPPER_A") (pin "OUT1A") (pinfunction "OUT1A_OUT1A") (pintype "output"))
    )
    (net (code "12") (name "A_OUT1B") (class "Default")
      (node (ref "MOTOR_A") (pin "1") (pinfunction "S_1") (pintype "passive"))
      (node (ref "STEPPER_A") (pin "OUT1B") (pinfunction "OUT1B_OUT1B") (pintype "output"))
    )
    (net (code "13") (name "A_OUT2A") (class "Default")
      (node (ref "MOTOR_A") (pin "3") (pinfunction "S_3") (pintype "passive"))
      (node (ref "STEPPER_A") (pin "OUT2A") (pinfunction "OUT2A_OUT2A") (pintype "output"))
    )
    (net (code "14") (name "A_OUT2B") (class "Default")
      (node (ref "MOTOR_A") (pin "4") (pinfunction "S_4") (pintype "passive"))
      (node (ref "STEPPER_A") (pin "OUT2B") (pinfunction "OUT2B_OUT2B") (pintype "output"))
    )
    (net (code "15") (name "A_STEP") (class "Default")
      (node (ref "IC2") (pin "56") (pinfunction "PD9_56") (pintype "bidirectional"))
      (node (ref "STEPPER_A") (pin "STEP") (pinfunction "STEP_STEP") (pintype "input"))
    )
    (net (code "16") (name "BOOT1") (class "Default")
      (node (ref "IC2") (pin "37") (pinfunction "PB2_37") (pintype "bidirectional"))
      (node (ref "R28") (pin "2") (pinfunction "2_2") (pintype "passive"))
    )
    (net (code "17") (name "B_DIR") (class "Default")
      (node (ref "IC2") (pin "64") (pinfunction "PC7_64") (pintype "bidirectional"))
      (node (ref "STEPPER_B") (pin "DIR") (pinfunction "DIR_DIR") (pintype "input"))
    )
    (net (code "18") (name "B_DIS") (class "Default")
      (node (ref "IC2") (pin "63") (pinfunction "PC6_63") (pintype "bidirectional"))
      (node (ref "R18") (pin "2") (pinfunction "2_2") (pintype "passive"))
      (node (ref "STEPPER_B") (pin "DIS") (pinfunction "DIS_DIS") (pintype "input"))
    )
    (net (code "19") (name "B_ENDST") (class "Default")
      (node (ref "IC1") (pin "3") (pinfunction "O_3") (pintype "output"))
      (node (ref "IC2") (pin "34") (pinfunction "PC5_34") (pintype "bidirectional"))
    )
    (net (code "20") (name "B_ENDSW") (class "Default")
      (node (ref "D2") (pin "A") (pinfunction "A_A") (pintype "passive"))
      (node (ref "R4") (pin "1") (pinfunction "1_1") (pintype "passive"))
      (node (ref "R5") (pin "1") (pinfunction "1_1") (pintype "passive"))
      (node (ref "X2") (pin "1") (pinfunction "S_1") (pintype "passive"))
    )
    (net (code "21") (name "B_MS1") (class "Default")
      (node (ref "IC2") (pin "57") (pinfunction "PD10_57") (pintype "bidirectional"))
      (node (ref "STEPPER_B") (pin "MS1") (pinfunction "MS1_MS1") (pintype "input"))
    )
    (net (code "22") (name "B_MS2") (class "Default")
      (node (ref "IC2") (pin "58") (pinfunction "PD11_58") (pintype "bidirectional"))
      (node (ref "STEPPER_B") (pin "MS2") (pinfunction "MS2_MS2") (pintype "input"))
    )
    (net (code "23") (name "B_OUT1A") (class "Default")
      (node (ref "MOTOR_B") (pin "2") (pinfunction "S_2") (pintype "passive"))
      (node (ref "STEPPER_B") (pin "OUT1A") (pinfunction "OUT1A_OUT1A") (pintype "output"))
    )
    (net (code "24") (name "B_OUT1B") (class "Default")
      (node (ref "MOTOR_B") (pin "1") (pinfunction "S_1") (pintype "passive"))
      (node (ref "STEPPER_B") (pin "OUT1B") (pinfunction "OUT1B_OUT1B") (pintype "output"))
    )
    (net (code "25") (name "B_OUT2A") (class "Default")
      (node (ref "MOTOR_B") (pin "3") (pinfunction "S_3") (pintype "passive"))
      (node (ref "STEPPER_B") (pin "OUT2A") (pinfunction "OUT2A_OUT2A") (pintype "output"))
    )
    (net (code "26") (name "B_OUT2B") (class "Default")
      (node (ref "MOTOR_B") (pin "4") (pinfunction "S_4") (pintype "passive"))
      (node (ref "STEPPER_B") (pin "OUT2B") (pinfunction "OUT2B_OUT2B") (pintype "output"))
    )
    (net (code "27") (name "B_STEP") (class "Default")
      (node (ref "IC2") (pin "65") (pinfunction "PC8_65") (pintype "bidirectional"))
      (node (ref "STEPPER_B") (pin "STEP") (pinfunction "STEP_STEP") (pintype "input"))
    )
    (net (code "28") (name "D_DIR") (class "Default")
      (node (ref "IC2") (pin "60") (pinfunction "PD13_60") (pintype "bidirectional"))
      (node (ref "STEPPER_D") (pin "DIR") (pinfunction "DIR_DIR") (pintype "input"))
    )
    (net (code "29") (name "D_DIS") (class "Default")
      (node (ref "IC2") (pin "59") (pinfunction "PD12_59") (pintype "bidirectional"))
      (node (ref "R26") (pin "2") (pinfunction "2_2") (pintype "passive"))
      (node (ref "STEPPER_D") (pin "DIS") (pinfunction "DIS_DIS") (pintype "input"))
    )
    (net (code "30") (name "D_ENDST") (class "Default")
      (node (ref "IC1") (pin "8") (pinfunction "O_8") (pintype "output"))
      (node (ref "IC2") (pin "8") (pinfunction "PC14_8") (pintype "bidirectional"))
    )
    (net (code "31") (name "D_ENDSW") (class "Default")
      (node (ref "D4") (pin "A") (pinfunction "A_A") (pintype "passive"))
      (node (ref "R8") (pin "1") (pinfunction "1_1") (pintype "passive"))
      (node (ref "R9") (pin "1") (pinfunction "1_1") (pintype "passive"))
      (node (ref "X4") (pin "1") (pinfunction "S_1") (pintype "passive"))
    )
    (net (code "32") (name "D_MS1") (class "Default")
      (node (ref "IC2") (pin "82") (pinfunction "PD1_82") (pintype "bidirectional"))
      (node (ref "STEPPER_D") (pin "MS1") (pinfunction "MS1_MS1") (pintype "input"))
    )
    (net (code "33") (name "D_MS2") (class "Default")
      (node (ref "IC2") (pin "83") (pinfunction "PD2_83") (pintype "bidirectional"))
      (node (ref "STEPPER_D") (pin "MS2") (pinfunction "MS2_MS2") (pintype "input"))
    )
    (net (code "34") (name "D_OUT1A") (class "Default")
      (node (ref "MOTOR_D") (pin "2") (pinfunction "S_2") (pintype "passive"))
      (node (ref "STEPPER_D") (pin "OUT1A") (pinfunction "OUT1A_OUT1A") (pintype "output"))
    )
    (net (code "35") (name "D_OUT1B") (class "Default")
      (node (ref "MOTOR_D") (pin "1") (pinfunction "S_1") (pintype "passive"))
      (node (ref "STEPPER_D") (pin "OUT1B") (pinfunction "OUT1B_OUT1B") (pintype "output"))
    )
    (net (code "36") (name "D_OUT2A") (class "Default")
      (node (ref "MOTOR_D") (pin "3") (pinfunction "S_3") (pintype "passive"))
      (node (ref "STEPPER_D") (pin "OUT2A") (pinfunction "OUT2A_OUT2A") (pintype "output"))
    )
    (net (code "37") (name "D_OUT2B") (class "Default")
      (node (ref "MOTOR_D") (pin "4") (pinfunction "S_4") (pintype "passive"))
      (node (ref "STEPPER_D") (pin "OUT2B") (pinfunction "OUT2B_OUT2B") (pintype "output"))
    )
    (net (code "38") (name "D_STEP") (class "Default")
      (node (ref "IC2") (pin "61") (pinfunction "PD14_61") (pintype "bidirectional"))
      (node (ref "STEPPER_D") (pin "STEP") (pinfunction "STEP_STEP") (pintype "input"))
    )
    (net (code "39") (name "EXT_3_3V") (class "Default")
      (node (ref "JP3") (pin "3") (pinfunction "3_3") (pintype "passive"))
      (node (ref "R33") (pin "2") (pinfunction "2_2") (pintype "passive"))
      (node (ref "R35") (pin "2") (pinfunction "2_2") (pintype "passive"))
    )
    (net (code "40") (name "GND") (class "Default")
      (node (ref "C1") (pin "2") (pinfunction "2_2") (pintype "passive"))
      (node (ref "C10") (pin "1") (pinfunction "1_1") (pintype "passive"))
      (node (ref "C11") (pin "1") (pinfunction "1_1") (pintype "passive"))
      (node (ref "C12") (pin "2") (pinfunction "2_2") (pintype "passive"))
      (node (ref "C13") (pin "2") (pinfunction "2_2") (pintype "passive"))
      (node (ref "C14") (pin "2") (pinfunction "2_2") (pintype "passive"))
      (node (ref "C15") (pin "-") (pinfunction "-_-") (pintype "passive"))
      (node (ref "C16") (pin "2") (pinfunction "2_2") (pintype "passive"))
      (node (ref "C17") (pin "2") (pinfunction "2_2") (pintype "passive"))
      (node (ref "C18") (pin "2") (pinfunction "2_2") (pintype "passive"))
      (node (ref "C19") (pin "2") (pinfunction "2_2") (pintype "passive"))
      (node (ref "C2") (pin "2") (pinfunction "2_2") (pintype "passive"))
      (node (ref "C3") (pin "2") (pinfunction "2_2") (pintype "passive"))
      (node (ref "C4") (pin "2") (pinfunction "2_2") (pintype "passive"))
      (node (ref "C5") (pin "2") (pinfunction "2_2") (pintype "passive"))
      (node (ref "C6") (pin "2") (pinfunction "2_2") (pintype "passive"))
      (node (ref "C7") (pin "2") (pinfunction "2_2") (pintype "passive"))
      (node (ref "C8") (pin "2") (pinfunction "2_2") (pintype "passive"))
      (node (ref "C9") (pin "2") (pinfunction "2_2") (pintype "passive"))
      (node (ref "D10") (pin "C") (pinfunction "C_C") (pintype "passive"))
      (node (ref "D9") (pin "C") (pinfunction "C_C") (pintype "passive"))
      (node (ref "IC1") (pin "7") (pinfunction "GND_7") (pintype "power_in"))
      (node (ref "IC2") (pin "10") (pinfunction "VSS_10") (pintype "power_in"))
      (node (ref "IC2") (pin "20") (pinfunction "VSSA_20") (pintype "power_in"))
      (node (ref "IC2") (pin "27") (pinfunction "VSS_27") (pintype "power_in"))
      (node (ref "IC2") (pin "74") (pinfunction "VSS_74") (pintype "power_in"))
      (node (ref "IC2") (pin "99") (pinfunction "VSS_99") (pintype "power_in"))
      (node (ref "IC3") (pin "1") (pinfunction "ADJ_1") (pintype "input"))
      (node (ref "PWR") (pin "3") (pinfunction "S_3") (pintype "passive"))
      (node (ref "PWR") (pin "4") (pinfunction "S_4") (pintype "passive"))
      (node (ref "R27") (pin "1") (pinfunction "1_1") (pintype "passive"))
      (node (ref "R28") (pin "1") (pinfunction "1_1") (pintype "passive"))
      (node (ref "R32") (pin "1") (pinfunction "1_1") (pintype "passive"))
      (node (ref "R36") (pin "1") (pinfunction "1_1") (pintype "passive"))
      (node (ref "RAP") (pin "13") (pinfunction "S_13") (pintype "passive"))
      (node (ref "RAP") (pin "14") (pinfunction "S_14") (pintype "passive"))
      (node (ref "STEPPER_A") (pin "GND") (pinfunction "GND_GND") (pintype "power_in"))
      (node (ref "STEPPER_B") (pin "GND") (pinfunction "GND_GND") (pintype "power_in"))
      (node (ref "STEPPER_D") (pin "GND") (pinfunction "GND_GND") (pintype "power_in"))
      (node (ref "STEPPER_G") (pin "GND") (pinfunction "GND_GND") (pintype "power_in"))
      (node (ref "SWD") (pin "6") (pinfunction "S_6") (pintype "passive"))
      (node (ref "T1") (pin "2") (pinfunction "E_2") (pintype "passive"))
      (node (ref "T10") (pin "2") (pinfunction "E_2") (pintype "passive"))
      (node (ref "T2") (pin "2") (pinfunction "E_2") (pintype "passive"))
      (node (ref "T3") (pin "2") (pinfunction "E_2") (pintype "passive"))
      (node (ref "T4") (pin "2") (pinfunction "E_2") (pintype "passive"))
      (node (ref "T5") (pin "2") (pinfunction "E_2") (pintype "passive"))
      (node (ref "T6") (pin "2") (pinfunction "E_2") (pintype "passive"))
      (node (ref "T7") (pin "2") (pinfunction "E_2") (pintype "passive"))
      (node (ref "T8") (pin "2") (pinfunction "E_2") (pintype "passive"))
      (node (ref "T9") (pin "2") (pinfunction "E_2") (pintype "passive"))
      (node (ref "X1") (pin "2") (pinfunction "S_2") (pintype "passive"))
      (node (ref "X2") (pin "2") (pinfunction "S_2") (pintype "passive"))
      (node (ref "X3") (pin "2") (pinfunction "S_2") (pintype "passive"))
      (node (ref "X4") (pin "2") (pinfunction "S_2") (pintype "passive"))
    )
    (net (code "41") (name "G_DIR") (class "Default")
      (node (ref "IC2") (pin "9") (pinfunction "PC15_9") (pintype "bidirectional"))
      (node (ref "STEPPER_G") (pin "DIR") (pinfunction "DIR_DIR") (pintype "input"))
    )
    (net (code "42") (name "G_DIS") (class "Default")
      (node (ref "IC2") (pin "80") (pinfunction "PC12_80") (pintype "bidirectional"))
      (node (ref "R22") (pin "2") (pinfunction "2_2") (pintype "passive"))
      (node (ref "STEPPER_G") (pin "DIS") (pinfunction "DIS_DIS") (pintype "input"))
    )
    (net (code "43") (name "G_ENDST") (class "Default")
      (node (ref "IC1") (pin "11") (pinfunction "O_11") (pintype "output"))
      (node (ref "IC2") (pin "7") (pinfunction "PC13_7") (pintype "bidirectional"))
    )
    (net (code "44") (name "G_ENDSW") (class "Default")
      (node (ref "D3") (pin "A") (pinfunction "A_A") (pintype "passive"))
      (node (ref "R6") (pin "1") (pinfunction "1_1") (pintype "passive"))
      (node (ref "R7") (pin "1") (pinfunction "1_1") (pintype "passive"))
      (node (ref "X3") (pin "1") (pinfunction "S_1") (pintype "passive"))
    )
    (net (code "45") (name "G_MS1") (class "Default")
      (node (ref "IC2") (pin "78") (pinfunction "PC10_78") (pintype "bidirectional"))
      (node (ref "STEPPER_G") (pin "MS1") (pinfunction "MS1_MS1") (pintype "input"))
    )
    (net (code "46") (name "G_MS2") (class "Default")
      (node (ref "IC2") (pin "79") (pinfunction "PC11_79") (pintype "bidirectional"))
      (node (ref "STEPPER_G") (pin "MS2") (pinfunction "MS2_MS2") (pintype "input"))
    )
    (net (code "47") (name "G_OUT1A") (class "Default")
      (node (ref "MOTOR_G") (pin "2") (pinfunction "S_2") (pintype "passive"))
      (node (ref "STEPPER_G") (pin "OUT1A") (pinfunction "OUT1A_OUT1A") (pintype "output"))
    )
    (net (code "48") (name "G_OUT1B") (class "Default")
      (node (ref "MOTOR_G") (pin "1") (pinfunction "S_1") (pintype "passive"))
      (node (ref "STEPPER_G") (pin "OUT1B") (pinfunction "OUT1B_OUT1B") (pintype "output"))
    )
    (net (code "49") (name "G_OUT2A") (class "Default")
      (node (ref "MOTOR_G") (pin "3") (pinfunction "S_3") (pintype "passive"))
      (node (ref "STEPPER_G") (pin "OUT2A") (pinfunction "OUT2A_OUT2A") (pintype "output"))
    )
    (net (code "50") (name "G_OUT2B") (class "Default")
      (node (ref "MOTOR_G") (pin "4") (pinfunction "S_4") (pintype "passive"))
      (node (ref "STEPPER_G") (pin "OUT2B") (pinfunction "OUT2B_OUT2B") (pintype "output"))
    )
    (net (code "51") (name "G_STEP") (class "Default")
      (node (ref "IC2") (pin "81") (pinfunction "PD0_81") (pintype "bidirectional"))
      (node (ref "STEPPER_G") (pin "STEP") (pinfunction "STEP_STEP") (pintype "input"))
    )
    (net (code "52") (name "NRST") (class "Default")
      (node (ref "IC2") (pin "14") (pinfunction "NRST_14") (pintype "bidirectional"))
      (node (ref "JP1") (pin "2") (pinfunction "2_2") (pintype "passive"))
    )
    (net (code "53") (name "Net-(D5-PadA)") (class "Default")
      (node (ref "D5") (pin "A") (pinfunction "A_A") (pintype "passive"))
      (node (ref "R13") (pin "1") (pinfunction "1_1") (pintype "passive"))
    )
    (net (code "54") (name "Net-(D6-PadA)") (class "Default")
      (node (ref "D6") (pin "A") (pinfunction "A_A") (pintype "passive"))
      (node (ref "R15") (pin "1") (pinfunction "1_1") (pintype "passive"))
    )
    (net (code "55") (name "Net-(D7-PadA)") (class "Default")
      (node (ref "D7") (pin "A") (pinfunction "A_A") (pintype "passive"))
      (node (ref "R19") (pin "1") (pinfunction "1_1") (pintype "passive"))
    )
    (net (code "56") (name "Net-(D8-PadA)") (class "Default")
      (node (ref "D8") (pin "A") (pinfunction "A_A") (pintype "passive"))
      (node (ref "R23") (pin "1") (pinfunction "1_1") (pintype "passive"))
    )
    (net (code "57") (name "Net-(D9-PadA)") (class "Default")
      (node (ref "D9") (pin "A") (pinfunction "A_A") (pintype "passive"))
      (node (ref "R10") (pin "1") (pinfunction "1_1") (pintype "passive"))
    )
    (net (code "58") (name "Net-(D10-PadA)") (class "Default")
      (node (ref "D10") (pin "A") (pinfunction "A_A") (pintype "passive"))
      (node (ref "R34") (pin "1") (pinfunction "1_1") (pintype "passive"))
    )
    (net (code "59") (name "Net-(IC1A-I1)") (class "Default")
      (node (ref "C2") (pin "1") (pinfunction "1_1") (pintype "passive"))
      (node (ref "D2") (pin "C") (pinfunction "C_C") (pintype "passive"))
      (node (ref "IC1") (pin "2") (pinfunction "I1_2") (pintype "input"))
      (node (ref "R5") (pin "2") (pinfunction "2_2") (pintype "passive"))
    )
    (net (code "60") (name "Net-(IC1B-I1)") (class "Default")
      (node (ref "C1") (pin "1") (pinfunction "1_1") (pintype "passive"))
      (node (ref "D1") (pin "C") (pinfunction "C_C") (pintype "passive"))
      (node (ref "IC1") (pin "5") (pinfunction "I1_5") (pintype "input"))
      (node (ref "R3") (pin "2") (pinfunction "2_2") (pintype "passive"))
    )
    (net (code "61") (name "Net-(IC1C-I1)") (class "Default")
      (node (ref "C4") (pin "1") (pinfunction "1_1") (pintype "passive"))
      (node (ref "D4") (pin "C") (pinfunction "C_C") (pintype "passive"))
      (node (ref "IC1") (pin "10") (pinfunction "I1_10") (pintype "input"))
      (node (ref "R9") (pin "2") (pinfunction "2_2") (pintype "passive"))
    )
    (net (code "62") (name "Net-(IC1D-I1)") (class "Default")
      (node (ref "C3") (pin "1") (pinfunction "1_1") (pintype "passive"))
      (node (ref "D3") (pin "C") (pinfunction "C_C") (pintype "passive"))
      (node (ref "IC1") (pin "13") (pinfunction "I1_13") (pintype "input"))
      (node (ref "R7") (pin "2") (pinfunction "2_2") (pintype "passive"))
    )
    (net (code "63") (name "Net-(IC3-OUT)") (class "Default")
      (node (ref "C15") (pin "+") (pinfunction "+_+") (pintype "passive"))
      (node (ref "IC3") (pin "4") (pinfunction "OUT_4") (pintype "passive"))
      (node (ref "R33") (pin "1") (pinfunction "1_1") (pintype "passive"))
    )
    (net (code "64") (name "Net-(Q1-G)") (class "Default")
      (node (ref "Q1") (pin "1") (pinfunction "G_1") (pintype "passive"))
      (node (ref "R30") (pin "1") (pinfunction "1_1") (pintype "passive"))
      (node (ref "T10") (pin "3") (pinfunction "C_3") (pintype "passive"))
    )
    (net (code "65") (name "Net-(SWDA-S)") (class "Default")
      (node (ref "R35") (pin "1") (pinfunction "1_1") (pintype "passive"))
      (node (ref "SWD") (pin "1") (pinfunction "S_1") (pintype "passive"))
    )
    (net (code "66") (name "Net-(T1-B)") (class "Default")
      (node (ref "R1") (pin "2") (pinfunction "2_2") (pintype "passive"))
      (node (ref "T1") (pin "1") (pinfunction "B_1") (pintype "passive"))
    )
    (net (code "67") (name "Net-(T1-C)") (class "Default")
      (node (ref "D11") (pin "A") (pinfunction "A_A") (pintype "passive"))
      (node (ref "K1") (pin "2") (pinfunction "2_2") (pintype "passive"))
      (node (ref "T1") (pin "3") (pinfunction "C_3") (pintype "passive"))
    )
    (net (code "68") (name "Net-(T2-B)") (class "Default")
      (node (ref "R11") (pin "1") (pinfunction "1_1") (pintype "passive"))
      (node (ref "T2") (pin "1") (pinfunction "B_1") (pintype "passive"))
    )
    (net (code "69") (name "Net-(T2-C)") (class "Default")
      (node (ref "D5") (pin "C") (pinfunction "C_C") (pintype "passive"))
      (node (ref "T2") (pin "3") (pinfunction "C_3") (pintype "passive"))
    )
    (net (code "70") (name "Net-(T3-B)") (class "Default")
      (node (ref "R14") (pin "1") (pinfunction "1_1") (pintype "passive"))
      (node (ref "T3") (pin "1") (pinfunction "B_1") (pintype "passive"))
    )
    (net (code "71") (name "Net-(T3-C)") (class "Default")
      (node (ref "R11") (pin "2") (pinfunction "2_2") (pintype "passive"))
      (node (ref "R12") (pin "2") (pinfunction "2_2") (pintype "passive"))
      (node (ref "T3") (pin "3") (pinfunction "C_3") (pintype "passive"))
    )
    (net (code "72") (name "Net-(T4-B)") (class "Default")
      (node (ref "R16") (pin "1") (pinfunction "1_1") (pintype "passive"))
      (node (ref "T4") (pin "1") (pinfunction "B_1") (pintype "passive"))
    )
    (net (code "73") (name "Net-(T4-C)") (class "Default")
      (node (ref "D6") (pin "C") (pinfunction "C_C") (pintype "passive"))
      (node (ref "T4") (pin "3") (pinfunction "C_3") (pintype "passive"))
    )
    (net (code "74") (name "Net-(T5-B)") (class "Default")
      (node (ref "R18") (pin "1") (pinfunction "1_1") (pintype "passive"))
      (node (ref "T5") (pin "1") (pinfunction "B_1") (pintype "passive"))
    )
    (net (code "75") (name "Net-(T5-C)") (class "Default")
      (node (ref "R16") (pin "2") (pinfunction "2_2") (pintype "passive"))
      (node (ref "R17") (pin "2") (pinfunction "2_2") (pintype "passive"))
      (node (ref "T5") (pin "3") (pinfunction "C_3") (pintype "passive"))
    )
    (net (code "76") (name "Net-(T6-B)") (class "Default")
      (node (ref "R20") (pin "1") (pinfunction "1_1") (pintype "passive"))
      (node (ref "T6") (pin "1") (pinfunction "B_1") (pintype "passive"))
    )
    (net (code "77") (name "Net-(T6-C)") (class "Default")
      (node (ref "D7") (pin "C") (pinfunction "C_C") (pintype "passive"))
      (node (ref "T6") (pin "3") (pinfunction "C_3") (pintype "passive"))
    )
    (net (code "78") (name "Net-(T7-B)") (class "Default")
      (node (ref "R22") (pin "1") (pinfunction "1_1") (pintype "passive"))
      (node (ref "T7") (pin "1") (pinfunction "B_1") (pintype "passive"))
    )
    (net (code "79") (name "Net-(T7-C)") (class "Default")
      (node (ref "R20") (pin "2") (pinfunction "2_2") (pintype "passive"))
      (node (ref "R21") (pin "2") (pinfunction "2_2") (pintype "passive"))
      (node (ref "T7") (pin "3") (pinfunction "C_3") (pintype "passive"))
    )
    (net (code "80") (name "Net-(T8-B)") (class "Default")
      (node (ref "R24") (pin "1") (pinfunction "1_1") (pintype "passive"))
      (node (ref "T8") (pin "1") (pinfunction "B_1") (pintype "passive"))
    )
    (net (code "81") (name "Net-(T8-C)") (class "Default")
      (node (ref "D8") (pin "C") (pinfunction "C_C") (pintype "passive"))
      (node (ref "T8") (pin "3") (pinfunction "C_3") (pintype "passive"))
    )
    (net (code "82") (name "Net-(T9-B)") (class "Default")
      (node (ref "R26") (pin "1") (pinfunction "1_1") (pintype "passive"))
      (node (ref "T9") (pin "1") (pinfunction "B_1") (pintype "passive"))
    )
    (net (code "83") (name "Net-(T9-C)") (class "Default")
      (node (ref "R24") (pin "2") (pinfunction "2_2") (pintype "passive"))
      (node (ref "R25") (pin "2") (pinfunction "2_2") (pintype "passive"))
      (node (ref "T9") (pin "3") (pinfunction "C_3") (pintype "passive"))
    )
    (net (code "84") (name "Net-(T10-B)") (class "Default")
      (node (ref "R31") (pin "1") (pinfunction "1_1") (pintype "passive"))
      (node (ref "R36") (pin "2") (pinfunction "2_2") (pintype "passive"))
      (node (ref "T10") (pin "1") (pinfunction "B_1") (pintype "passive"))
    )
    (net (code "85") (name "OSC_IN") (class "Default")
      (node (ref "C10") (pin "2") (pinfunction "2_2") (pintype "passive"))
      (node (ref "IC2") (pin "12") (pinfunction "OSC_IN_12") (pintype "bidirectional"))
      (node (ref "Y1") (pin "P$2") (pinfunction "2_P$2") (pintype "passive"))
    )
    (net (code "86") (name "OSC_OUT") (class "Default")
      (node (ref "C11") (pin "2") (pinfunction "2_2") (pintype "passive"))
      (node (ref "IC2") (pin "13") (pinfunction "OSC_OUT_13") (pintype "bidirectional"))
      (node (ref "Y1") (pin "P$1") (pinfunction "1_P$1") (pintype "passive"))
    )
    (net (code "87") (name "RAP_3_3V") (class "Default")
      (node (ref "JP3") (pin "1") (pinfunction "1_1") (pintype "passive"))
      (node (ref "RAP") (pin "1") (pinfunction "S_1") (pintype "passive"))
      (node (ref "RAP") (pin "2") (pinfunction "S_2") (pintype "passive"))
    )
    (net (code "88") (name "RAP_BOOTSEL") (class "Default")
      (node (ref "IC2") (pin "94") (pinfunction "BOOT0_94") (pintype "input"))
      (node (ref "R29") (pin "1") (pinfunction "1_1") (pintype "passive"))
      (node (ref "RAP") (pin "9") (pinfunction "S_9") (pintype "passive"))
    )
    (net (code "89") (name "RAP_ENBL") (class "Default")
      (node (ref "JP2") (pin "1") (pinfunction "1_1") (pintype "passive"))
      (node (ref "RAP") (pin "3") (pinfunction "S_3") (pintype "passive"))
    )
    (net (code "90") (name "RAP_INT0") (class "Default")
      (node (ref "IC2") (pin "16") (pinfunction "PC1_16") (pintype "bidirectional"))
      (node (ref "RAP") (pin "10") (pinfunction "S_10") (pintype "passive"))
    )
    (net (code "91") (name "RAP_INT1") (class "Default")
      (node (ref "IC2") (pin "84") (pinfunction "PD3_84") (pintype "bidirectional"))
      (node (ref "RAP") (pin "11") (pinfunction "S_11") (pintype "passive"))
    )
    (net (code "92") (name "RAP_INT2") (class "Default")
      (node (ref "IC2") (pin "85") (pinfunction "PD4_85") (pintype "bidirectional"))
      (node (ref "RAP") (pin "12") (pinfunction "S_12") (pintype "passive"))
    )
    (net (code "93") (name "RAP_NRST") (class "Default")
      (node (ref "JP1") (pin "1") (pinfunction "1_1") (pintype "passive"))
      (node (ref "RAP") (pin "4") (pinfunction "S_4") (pintype "passive"))
    )
    (net (code "94") (name "SPI_MISO") (class "Default")
      (node (ref "IC2") (pin "17") (pinfunction "PC2_17") (pintype "bidirectional"))
      (node (ref "RAP") (pin "8") (pinfunction "S_8") (pintype "passive"))
    )
    (net (code "95") (name "SPI_MOSI") (class "Default")
      (node (ref "IC2") (pin "18") (pinfunction "PC3_18") (pintype "bidirectional"))
      (node (ref "RAP") (pin "7") (pinfunction "S_7") (pintype "passive"))
    )
    (net (code "96") (name "SPI_NSS") (class "Default")
      (node (ref "IC2") (pin "51") (pinfunction "PB12_51") (pintype "bidirectional"))
      (node (ref "RAP") (pin "5") (pinfunction "S_5") (pintype "passive"))
    )
    (net (code "97") (name "SPI_SCK") (class "Default")
      (node (ref "IC2") (pin "47") (pinfunction "PB10_47") (pintype "bidirectional"))
      (node (ref "RAP") (pin "6") (pinfunction "S_6") (pintype "passive"))
    )
    (net (code "98") (name "SUPPLY_3_3V") (class "Default")
      (node (ref "JP2") (pin "3") (pinfunction "3_3") (pintype "passive"))
      (node (ref "JP3") (pin "2") (pinfunction "2_2") (pintype "passive"))
      (node (ref "Q1") (pin "2") (pinfunction "S_2") (pintype "passive"))
      (node (ref "R30") (pin "2") (pinfunction "2_2") (pintype "passive"))
    )
    (net (code "99") (name "SUPPLY_5V") (class "Default")
      (node (ref "C14") (pin "1") (pinfunction "1_1") (pintype "passive"))
      (node (ref "IC3") (pin "3") (pinfunction "IN_3") (pintype "input"))
      (node (ref "PWR") (pin "2") (pinfunction "S_2") (pintype "passive"))
    )
    (net (code "100") (name "SUPPLY_12V") (class "Default")
      (node (ref "D11") (pin "C") (pinfunction "C_C") (pintype "passive"))
      (node (ref "K1") (pin "1") (pinfunction "1_1") (pintype "passive"))
      (node (ref "K1") (pin "C") (pinfunction "P_C") (pintype "passive"))
      (node (ref "PWR") (pin "1") (pinfunction "S_1") (pintype "passive"))
    )
    (net (code "101") (name "SWCLK") (class "Default")
      (node (ref "IC2") (pin "76") (pinfunction "PA14_76") (pintype "bidirectional"))
      (node (ref "SWD") (pin "2") (pinfunction "S_2") (pintype "passive"))
    )
    (net (code "102") (name "SWDIO") (class "Default")
      (node (ref "IC2") (pin "72") (pinfunction "PA13_72") (pintype "bidirectional"))
      (node (ref "SWD") (pin "3") (pinfunction "S_3") (pintype "passive"))
    )
    (net (code "103") (name "SWD_NRST") (class "Default")
      (node (ref "JP1") (pin "3") (pinfunction "3_3") (pintype "passive"))
      (node (ref "SWD") (pin "4") (pinfunction "S_4") (pintype "passive"))
    )
    (net (code "104") (name "SWO") (class "Default")
      (node (ref "IC2") (pin "89") (pinfunction "PB3_89") (pintype "bidirectional"))
      (node (ref "SWD") (pin "5") (pinfunction "S_5") (pintype "passive"))
    )
    (net (code "105") (name "VBAT") (class "Default")
      (node (ref "IC2") (pin "6") (pinfunction "VBAT_6") (pintype "power_in"))
    )
    (net (code "106") (name "VCAP_1") (class "Default")
      (node (ref "C12") (pin "1") (pinfunction "1_1") (pintype "passive"))
      (node (ref "IC2") (pin "73") (pinfunction "VCAP2_73") (pintype "power_in"))
    )
    (net (code "107") (name "VCAP_2") (class "Default")
      (node (ref "C13") (pin "1") (pinfunction "1_1") (pintype "passive"))
      (node (ref "IC2") (pin "49") (pinfunction "VCAP1_49") (pintype "power_in"))
    )
    (net (code "108") (name "unconnected-(IC2A-PA0-Pad23)") (class "Default")
      (node (ref "IC2") (pin "23") (pinfunction "PA0_23") (pintype "bidirectional"))
    )
    (net (code "109") (name "unconnected-(IC2A-PA1-Pad24)") (class "Default")
      (node (ref "IC2") (pin "24") (pinfunction "PA1_24") (pintype "bidirectional"))
    )
    (net (code "110") (name "unconnected-(IC2A-PA2-Pad25)") (class "Default")
      (node (ref "IC2") (pin "25") (pinfunction "PA2_25") (pintype "bidirectional"))
    )
    (net (code "111") (name "unconnected-(IC2A-PA3-Pad26)") (class "Default")
      (node (ref "IC2") (pin "26") (pinfunction "PA3_26") (pintype "bidirectional"))
    )
    (net (code "112") (name "unconnected-(IC2A-PA4-Pad29)") (class "Default")
      (node (ref "IC2") (pin "29") (pinfunction "PA4_29") (pintype "bidirectional"))
    )
    (net (code "113") (name "unconnected-(IC2A-PA5-Pad30)") (class "Default")
      (node (ref "IC2") (pin "30") (pinfunction "PA5_30") (pintype "bidirectional"))
    )
    (net (code "114") (name "unconnected-(IC2A-PA6-Pad31)") (class "Default")
      (node (ref "IC2") (pin "31") (pinfunction "PA6_31") (pintype "bidirectional"))
    )
    (net (code "115") (name "unconnected-(IC2A-PA7-Pad32)") (class "Default")
      (node (ref "IC2") (pin "32") (pinfunction "PA7_32") (pintype "bidirectional"))
    )
    (net (code "116") (name "unconnected-(IC2A-PA8-Pad67)") (class "Default")
      (node (ref "IC2") (pin "67") (pinfunction "PA8_67") (pintype "bidirectional"))
    )
    (net (code "117") (name "unconnected-(IC2A-PA9-Pad68)") (class "Default")
      (node (ref "IC2") (pin "68") (pinfunction "PA9_68") (pintype "bidirectional"))
    )
    (net (code "118") (name "unconnected-(IC2A-PA10-Pad69)") (class "Default")
      (node (ref "IC2") (pin "69") (pinfunction "PA10_69") (pintype "bidirectional"))
    )
    (net (code "119") (name "unconnected-(IC2A-PA11-Pad70)") (class "Default")
      (node (ref "IC2") (pin "70") (pinfunction "PA11_70") (pintype "bidirectional"))
    )
    (net (code "120") (name "unconnected-(IC2A-PA12-Pad71)") (class "Default")
      (node (ref "IC2") (pin "71") (pinfunction "PA12_71") (pintype "bidirectional"))
    )
    (net (code "121") (name "unconnected-(IC2A-PA15-Pad77)") (class "Default")
      (node (ref "IC2") (pin "77") (pinfunction "PA15_77") (pintype "bidirectional"))
    )
    (net (code "122") (name "unconnected-(IC2A-PB0-Pad35)") (class "Default")
      (node (ref "IC2") (pin "35") (pinfunction "PB0_35") (pintype "bidirectional"))
    )
    (net (code "123") (name "unconnected-(IC2A-PB1-Pad36)") (class "Default")
      (node (ref "IC2") (pin "36") (pinfunction "PB1_36") (pintype "bidirectional"))
    )
    (net (code "124") (name "unconnected-(IC2A-PB4-Pad90)") (class "Default")
      (node (ref "IC2") (pin "90") (pinfunction "PB4_90") (pintype "bidirectional"))
    )
    (net (code "125") (name "unconnected-(IC2A-PB5-Pad91)") (class "Default")
      (node (ref "IC2") (pin "91") (pinfunction "PB5_91") (pintype "bidirectional"))
    )
    (net (code "126") (name "unconnected-(IC2A-PB6-Pad92)") (class "Default")
      (node (ref "IC2") (pin "92") (pinfunction "PB6_92") (pintype "bidirectional"))
    )
    (net (code "127") (name "unconnected-(IC2A-PB7-Pad93)") (class "Default")
      (node (ref "IC2") (pin "93") (pinfunction "PB7_93") (pintype "bidirectional"))
    )
    (net (code "128") (name "unconnected-(IC2A-PB8-Pad95)") (class "Default")
      (node (ref "IC2") (pin "95") (pinfunction "PB8_95") (pintype "bidirectional"))
    )
    (net (code "129") (name "unconnected-(IC2A-PB9-Pad96)") (class "Default")
      (node (ref "IC2") (pin "96") (pinfunction "PB9_96") (pintype "bidirectional"))
    )
    (net (code "130") (name "unconnected-(IC2A-PB11-Pad48)") (class "Default")
      (node (ref "IC2") (pin "48") (pinfunction "PB11_48") (pintype "bidirectional"))
    )
    (net (code "131") (name "unconnected-(IC2A-PB13-Pad52)") (class "Default")
      (node (ref "IC2") (pin "52") (pinfunction "PB13_52") (pintype "bidirectional"))
    )
    (net (code "132") (name "unconnected-(IC2A-PB14-Pad53)") (class "Default")
      (node (ref "IC2") (pin "53") (pinfunction "PB14_53") (pintype "bidirectional"))
    )
    (net (code "133") (name "unconnected-(IC2A-PB15-Pad54)") (class "Default")
      (node (ref "IC2") (pin "54") (pinfunction "PB15_54") (pintype "bidirectional"))
    )
    (net (code "134") (name "unconnected-(IC2A-PC9-Pad66)") (class "Default")
      (node (ref "IC2") (pin "66") (pinfunction "PC9_66") (pintype "bidirectional"))
    )
    (net (code "135") (name "unconnected-(IC2A-PD15-Pad62)") (class "Default")
      (node (ref "IC2") (pin "62") (pinfunction "PD15_62") (pintype "bidirectional"))
    )
    (net (code "136") (name "unconnected-(IC2A-PE0-Pad97)") (class "Default")
      (node (ref "IC2") (pin "97") (pinfunction "PE0_97") (pintype "bidirectional"))
    )
    (net (code "137") (name "unconnected-(IC2A-PE1-Pad98)") (class "Default")
      (node (ref "IC2") (pin "98") (pinfunction "PE1_98") (pintype "bidirectional"))
    )
    (net (code "138") (name "unconnected-(IC2A-PE2-Pad1)") (class "Default")
      (node (ref "IC2") (pin "1") (pinfunction "PE2_1") (pintype "bidirectional"))
    )
    (net (code "139") (name "unconnected-(IC2A-PE3-Pad2)") (class "Default")
      (node (ref "IC2") (pin "2") (pinfunction "PE3_2") (pintype "bidirectional"))
    )
    (net (code "140") (name "unconnected-(IC2A-PE4-Pad3)") (class "Default")
      (node (ref "IC2") (pin "3") (pinfunction "PE4_3") (pintype "bidirectional"))
    )
    (net (code "141") (name "unconnected-(IC2A-PE5-Pad4)") (class "Default")
      (node (ref "IC2") (pin "4") (pinfunction "PE5_4") (pintype "bidirectional"))
    )
    (net (code "142") (name "unconnected-(IC2A-PE6-Pad5)") (class "Default")
      (node (ref "IC2") (pin "5") (pinfunction "PE6_5") (pintype "bidirectional"))
    )
    (net (code "143") (name "unconnected-(IC2A-PE7-Pad38)") (class "Default")
      (node (ref "IC2") (pin "38") (pinfunction "PE7_38") (pintype "bidirectional"))
    )
    (net (code "144") (name "unconnected-(IC2A-PE8-Pad39)") (class "Default")
      (node (ref "IC2") (pin "39") (pinfunction "PE8_39") (pintype "bidirectional"))
    )
    (net (code "145") (name "unconnected-(IC2A-PE9-Pad40)") (class "Default")
      (node (ref "IC2") (pin "40") (pinfunction "PE9_40") (pintype "bidirectional"))
    )
    (net (code "146") (name "unconnected-(IC2A-PE10-Pad41)") (class "Default")
      (node (ref "IC2") (pin "41") (pinfunction "PE10_41") (pintype "bidirectional"))
    )
    (net (code "147") (name "unconnected-(IC2A-PE11-Pad42)") (class "Default")
      (node (ref "IC2") (pin "42") (pinfunction "PE11_42") (pintype "bidirectional"))
    )
    (net (code "148") (name "unconnected-(IC2A-PE12-Pad43)") (class "Default")
      (node (ref "IC2") (pin "43") (pinfunction "PE12_43") (pintype "bidirectional"))
    )
    (net (code "149") (name "unconnected-(IC2A-PE13-Pad44)") (class "Default")
      (node (ref "IC2") (pin "44") (pinfunction "PE13_44") (pintype "bidirectional"))
    )
    (net (code "150") (name "unconnected-(IC2A-PE14-Pad45)") (class "Default")
      (node (ref "IC2") (pin "45") (pinfunction "PE14_45") (pintype "bidirectional"))
    )
    (net (code "151") (name "unconnected-(IC2A-PE15-Pad46)") (class "Default")
      (node (ref "IC2") (pin "46") (pinfunction "PE15_46") (pintype "bidirectional"))
    )
    (net (code "152") (name "unconnected-(K1B-O-PadNC)") (class "Default")
      (node (ref "K1") (pin "NC") (pinfunction "O_NC") (pintype "passive"))
    )
  )
)
